# Versie_5.net
KiCad netlist of a schematic drawn in EAGLE
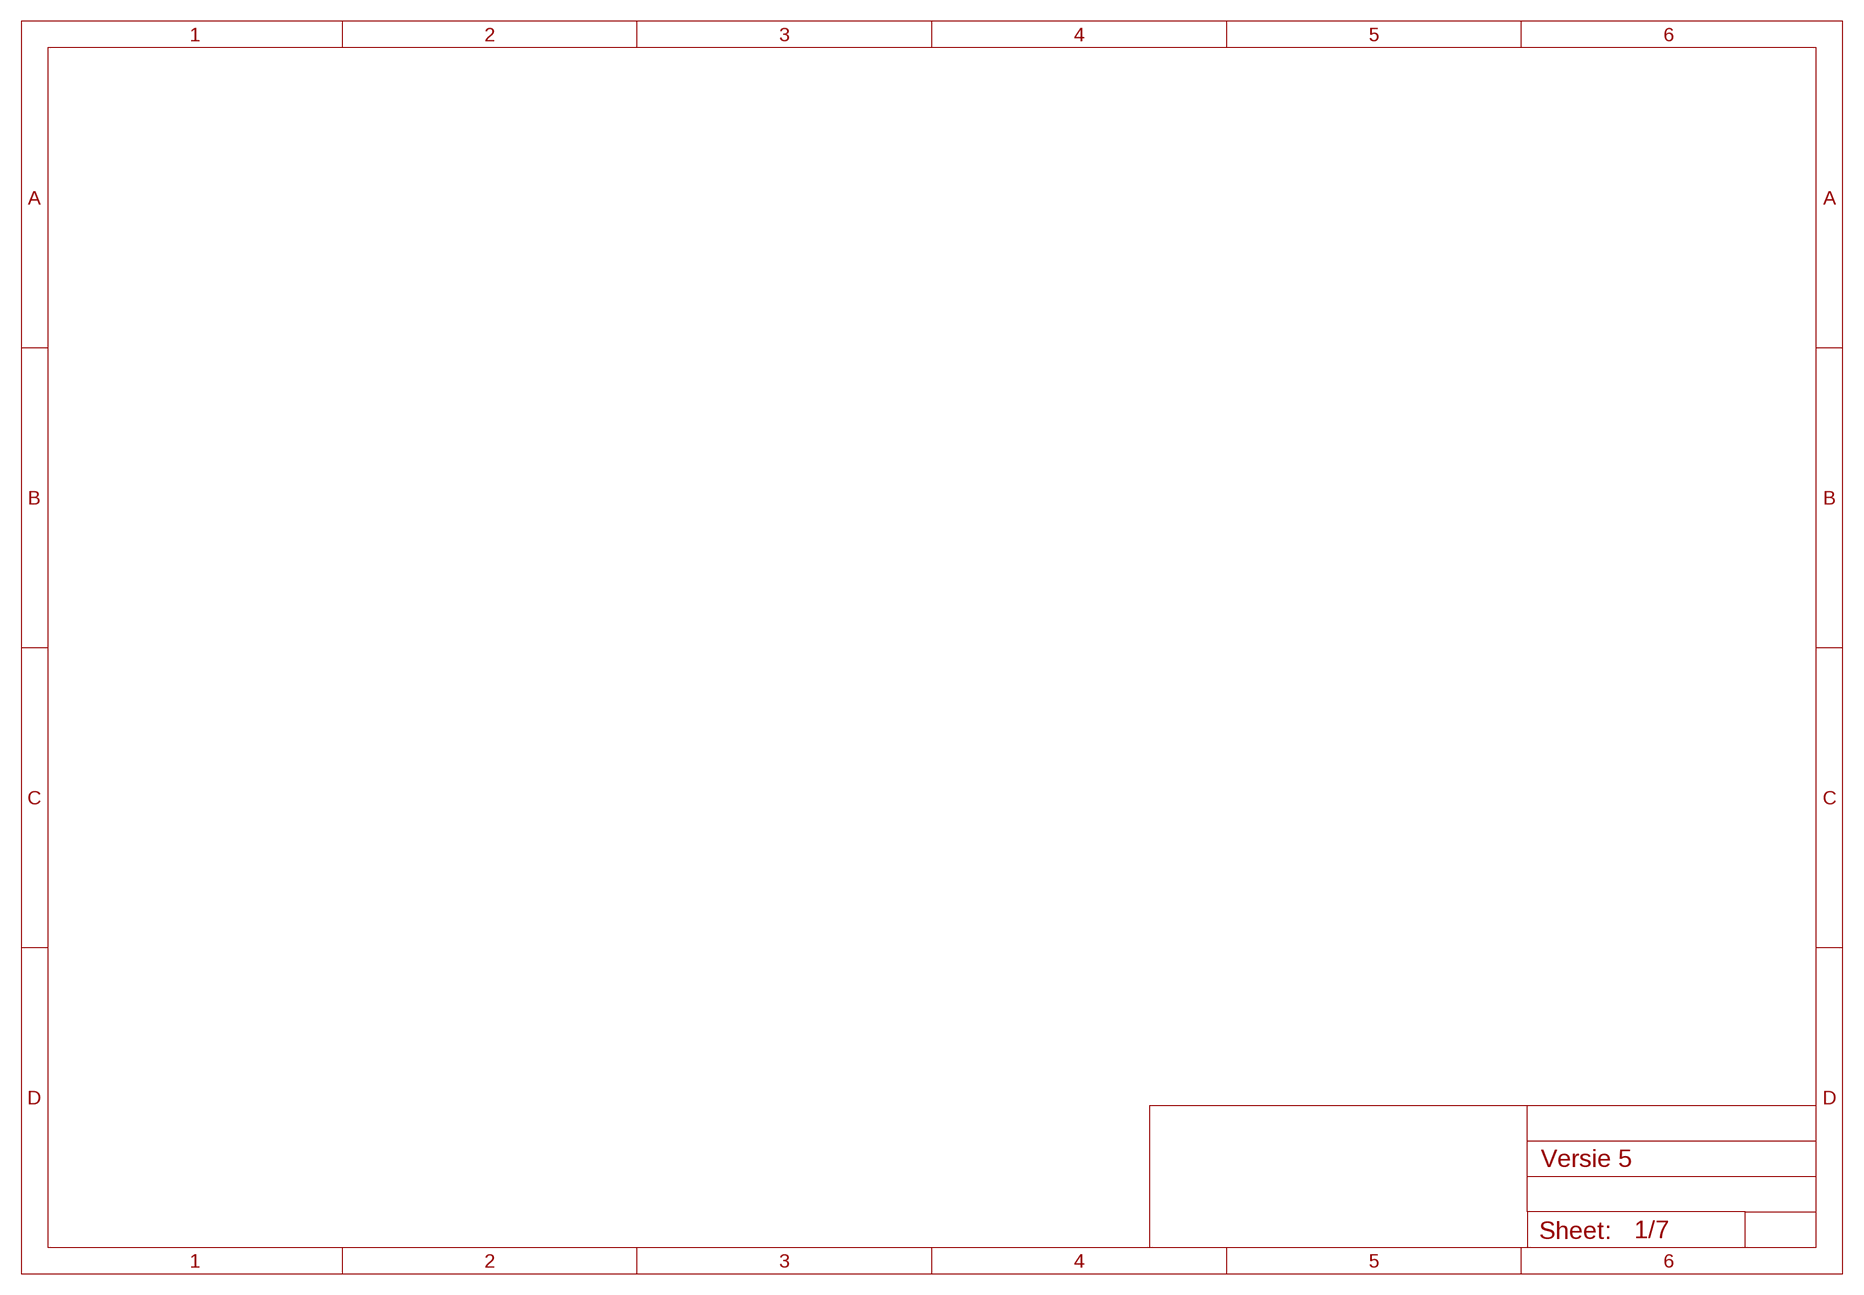
[diagram p0: schematic, sheet 1]
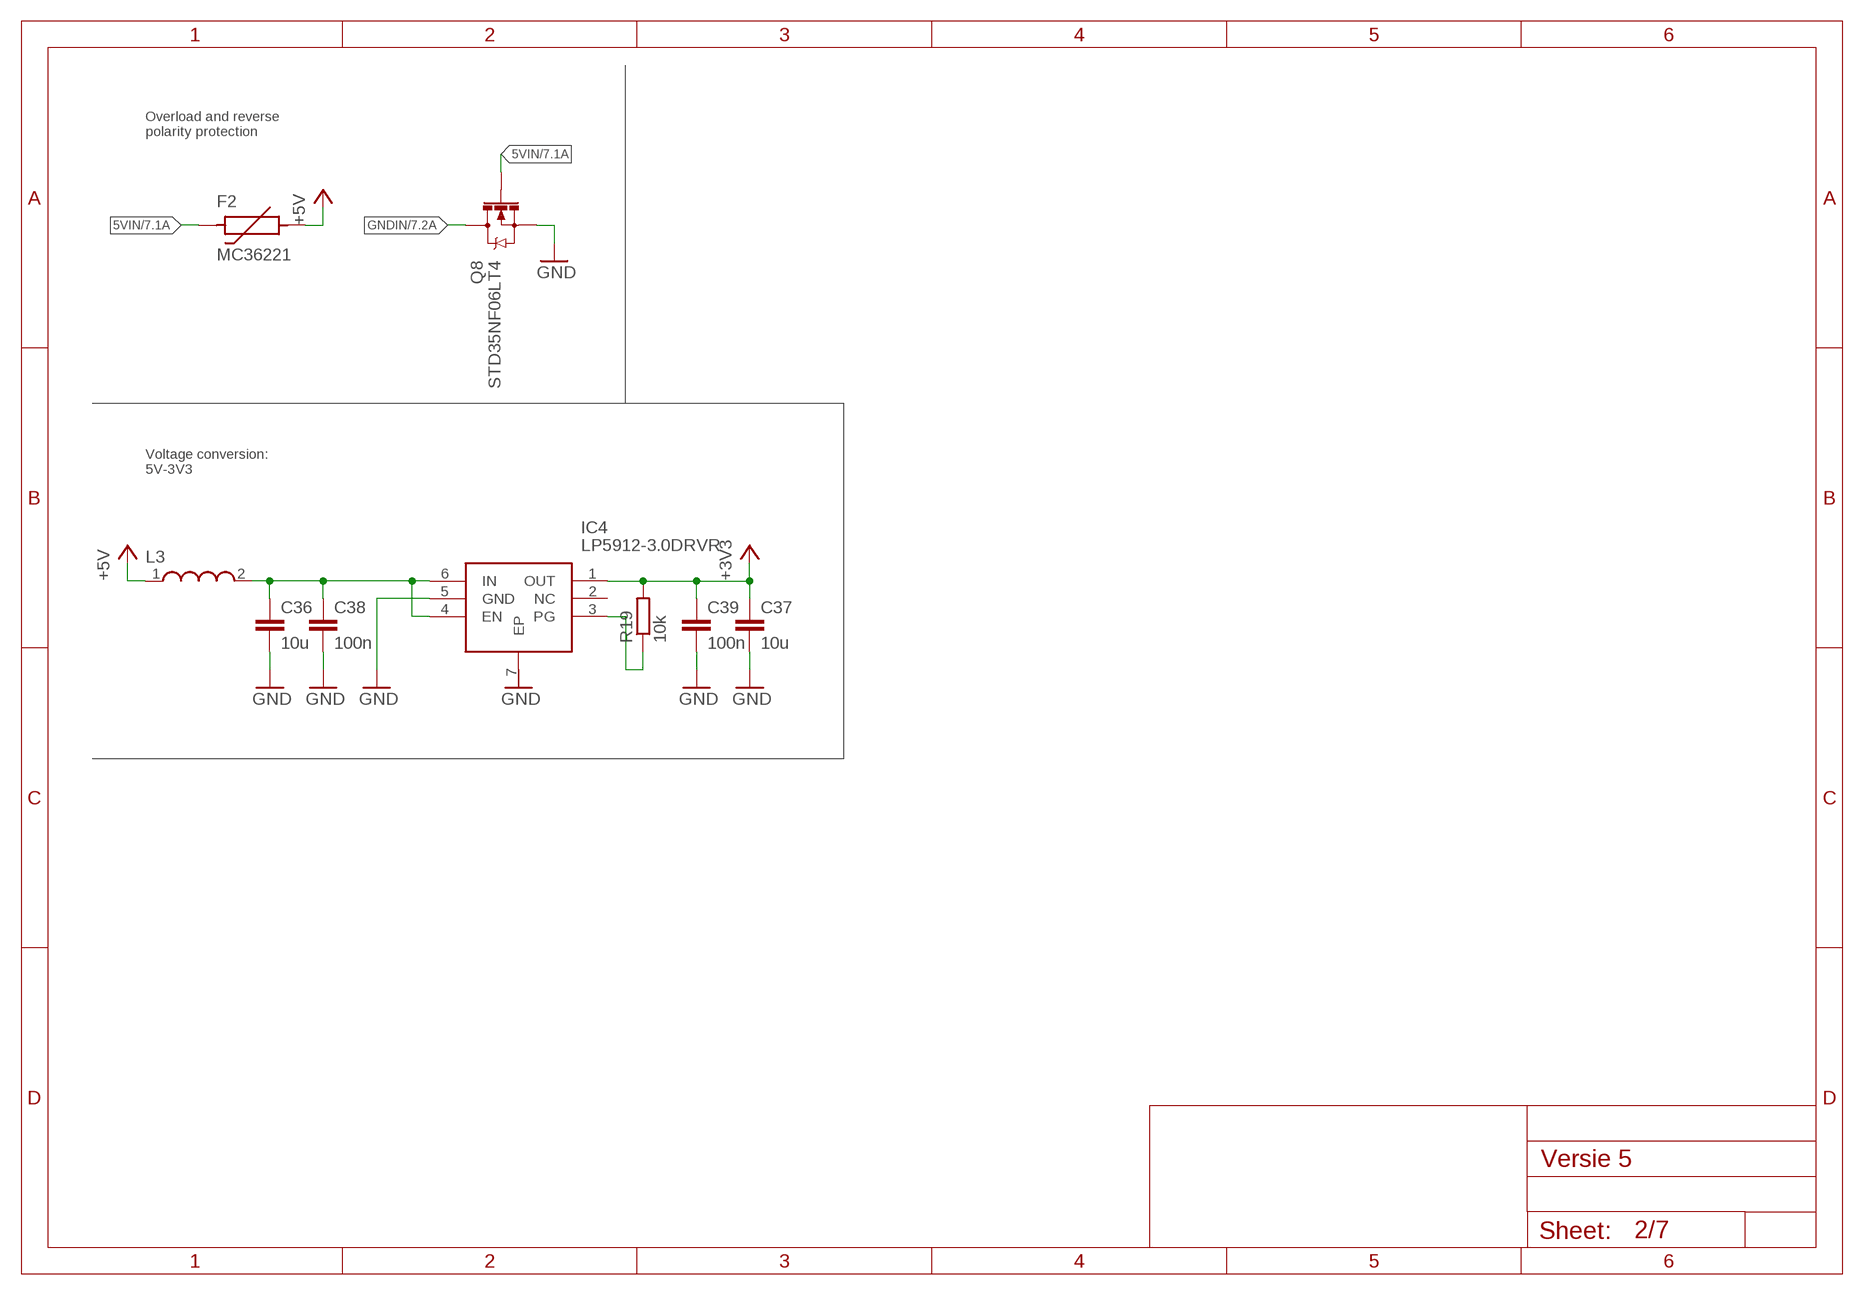
[diagram p1: schematic, sheet 2]
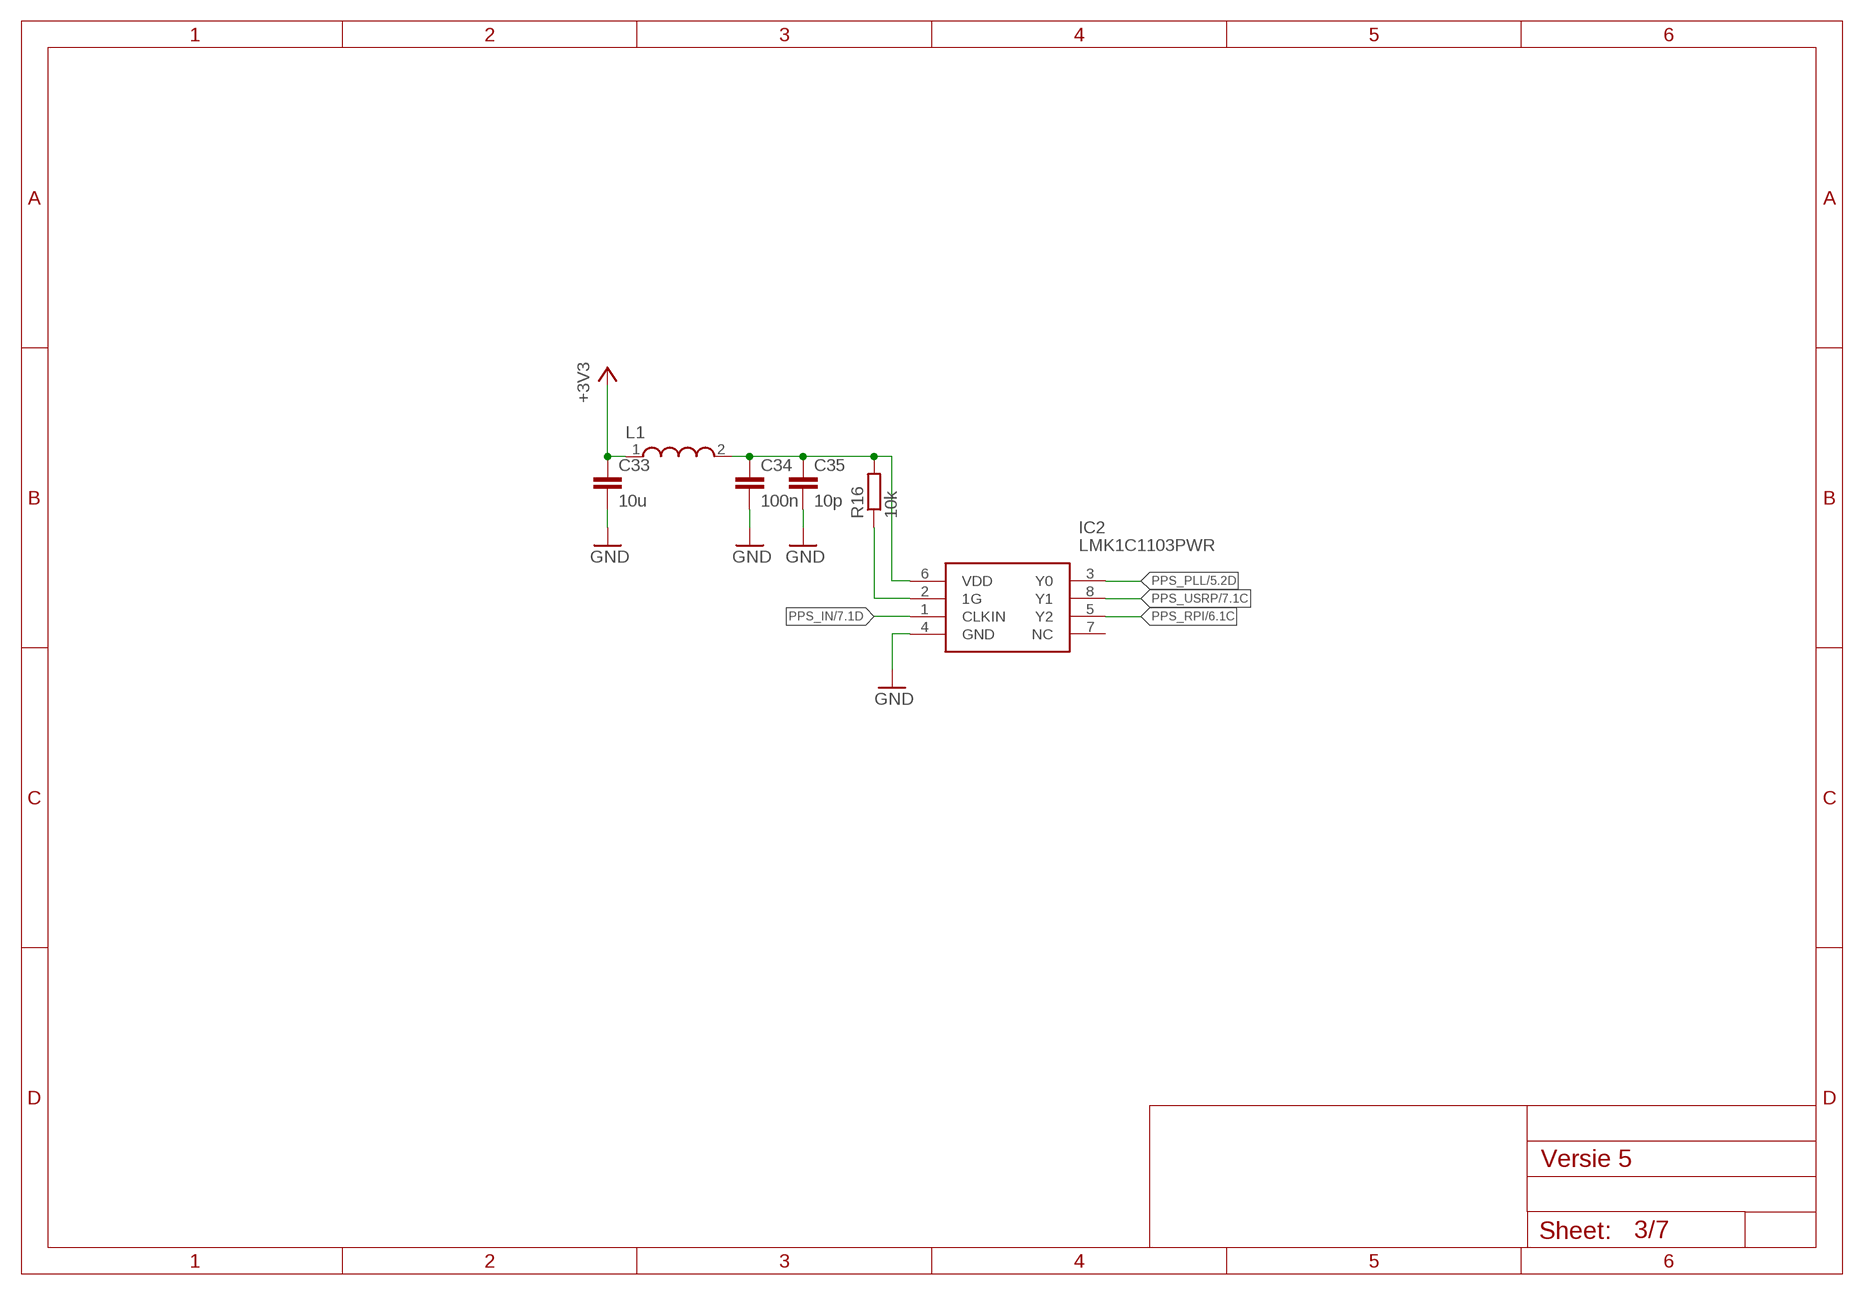
[diagram p2: schematic, sheet 3]
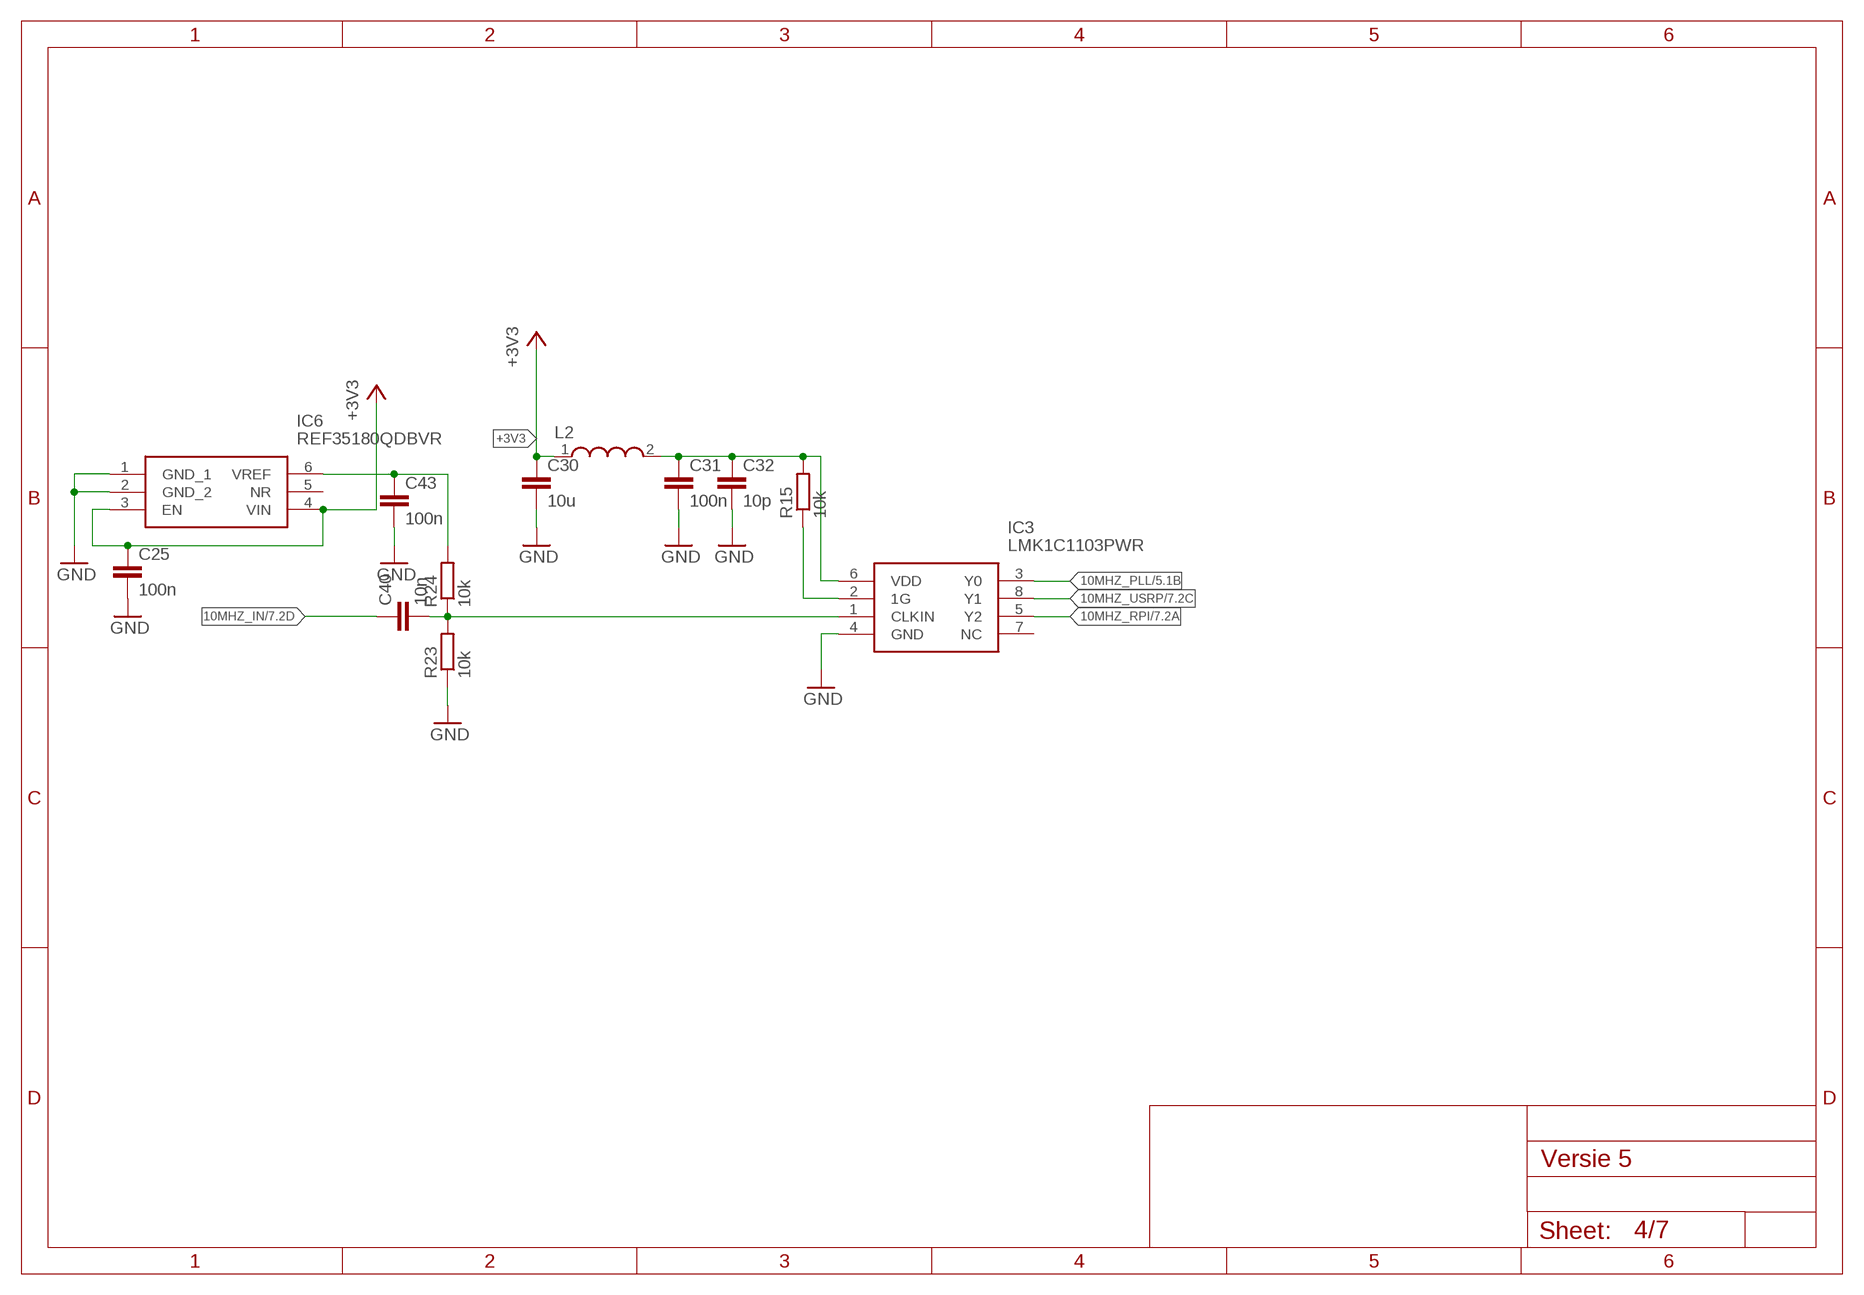
[diagram p3: schematic, sheet 4]
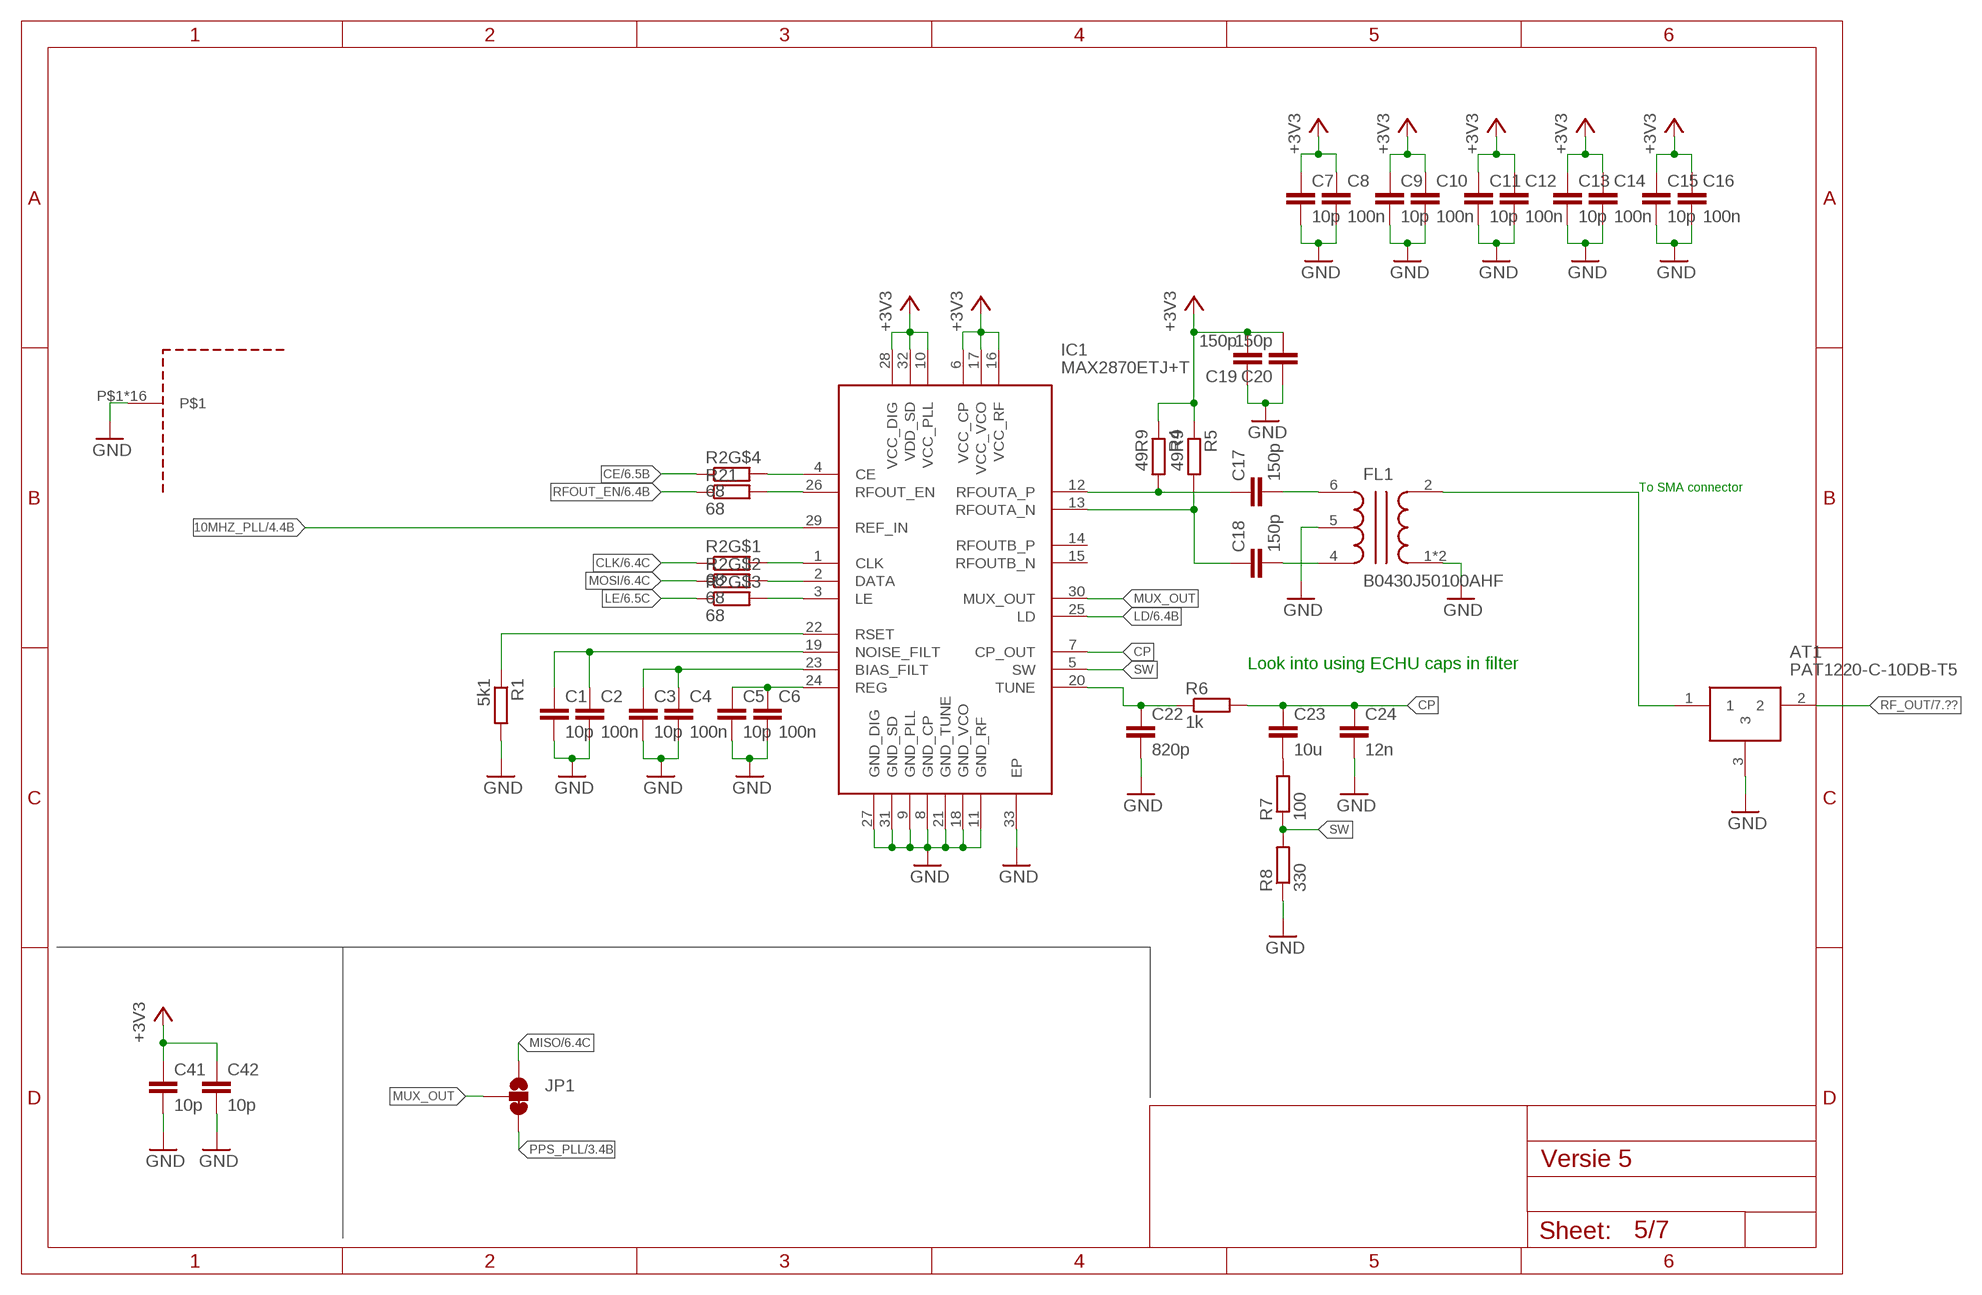
[diagram p4: schematic, sheet 5]
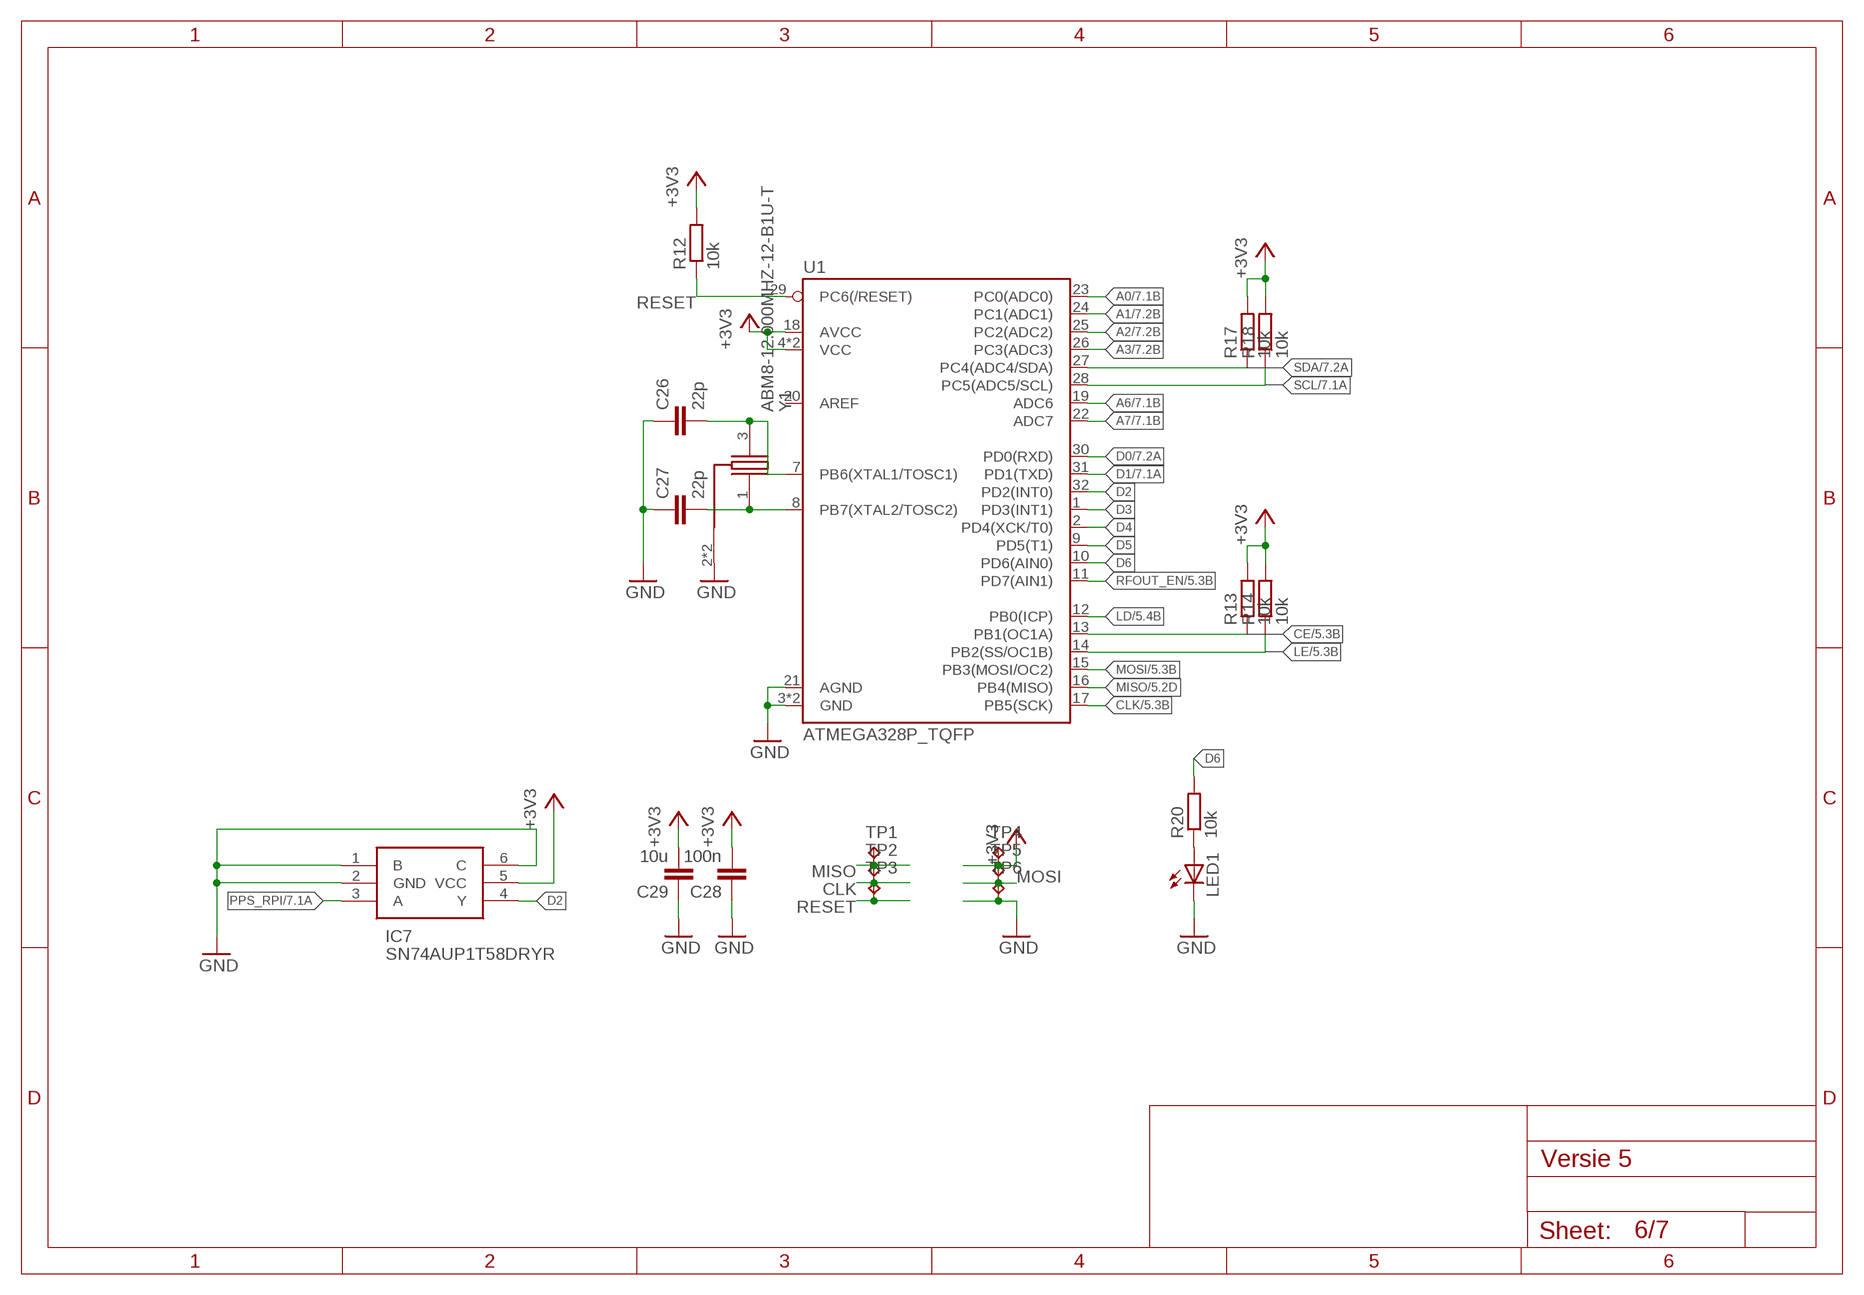
[diagram p5: schematic, sheet 6]
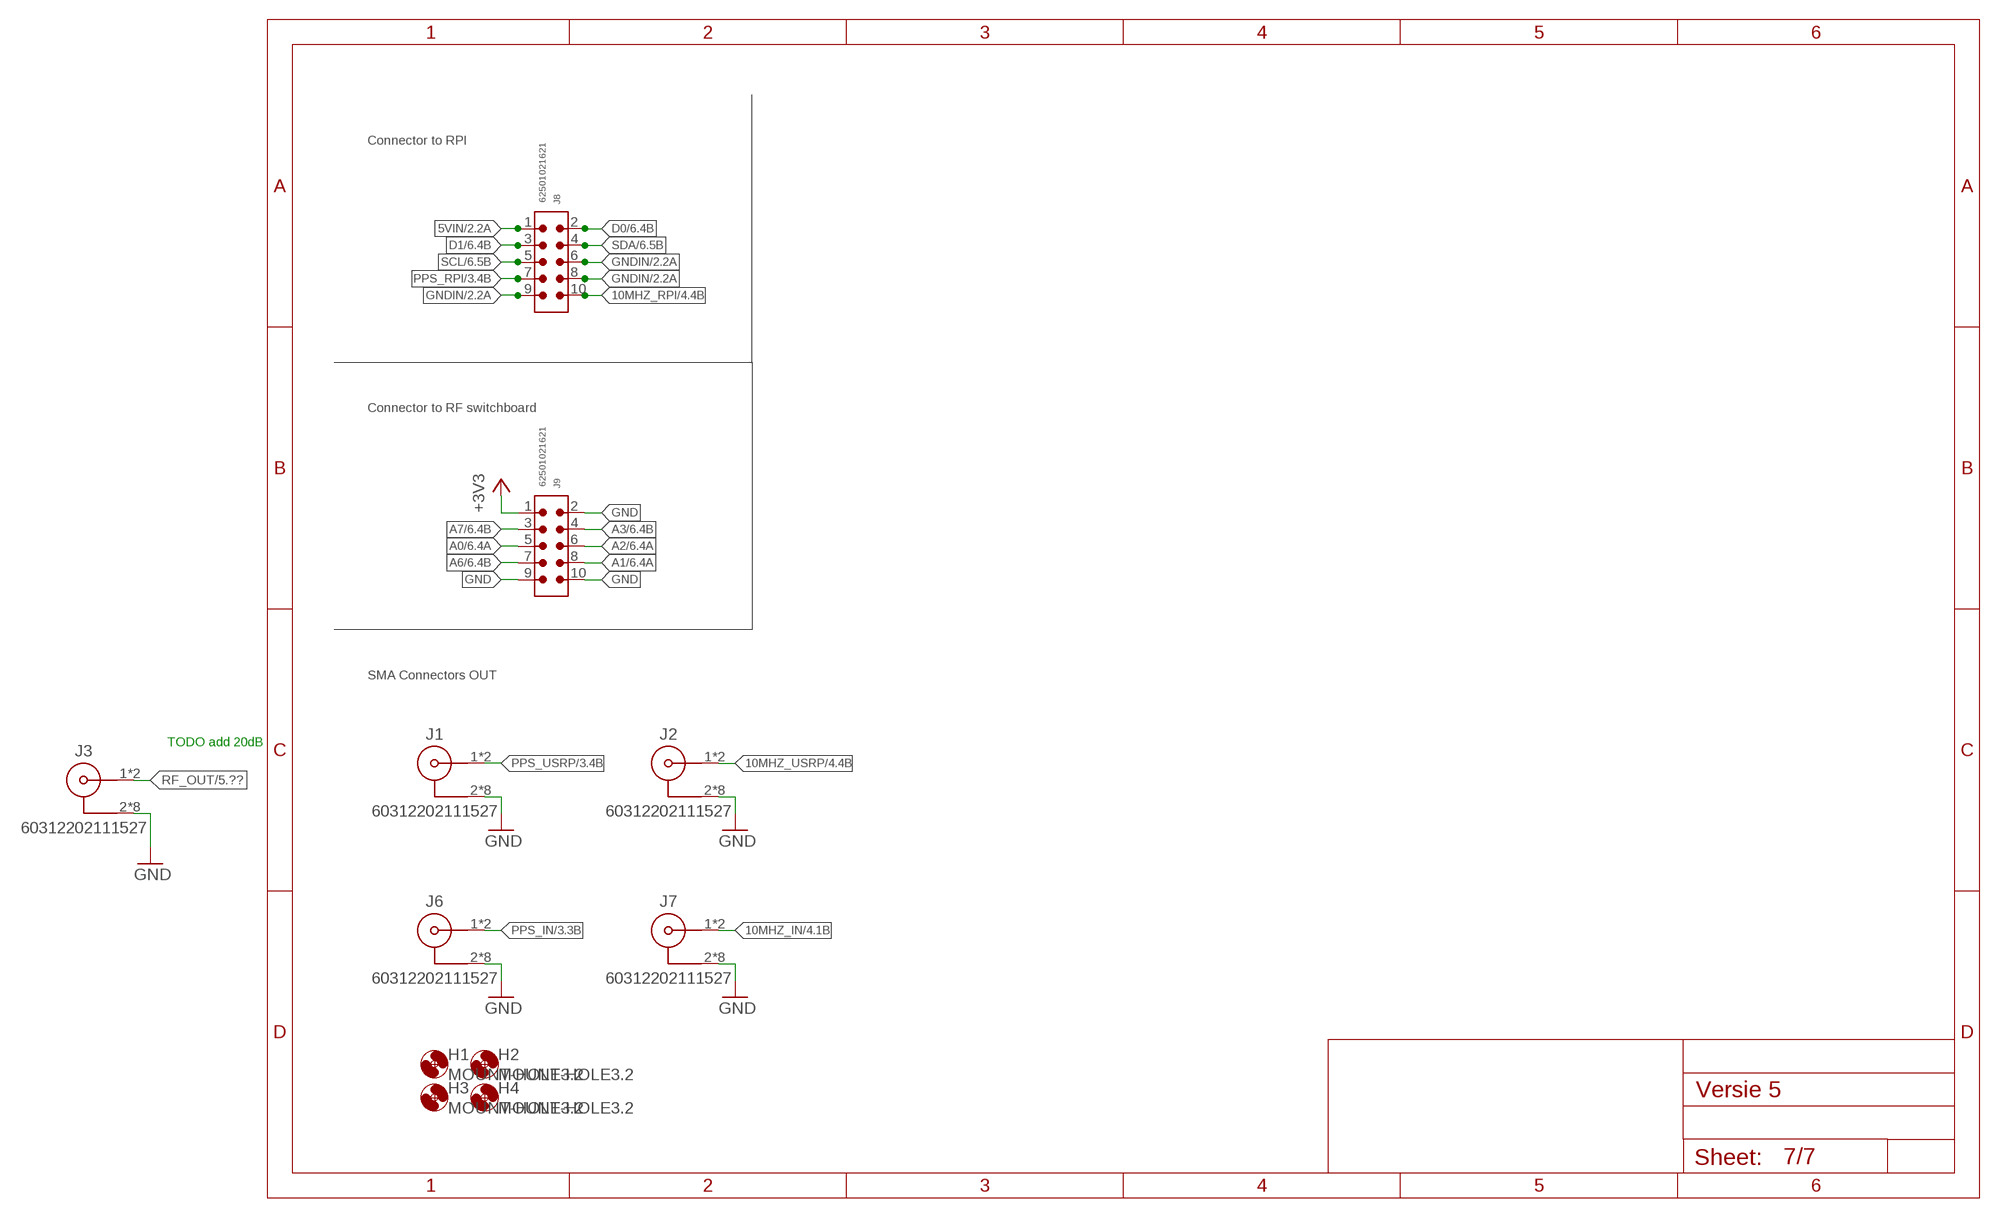
[diagram p6: schematic, sheet 7]

(export (version "E")
  (design (tool "Eeschema 10.0.6"))
  (components
    (comp (ref "C36")
      (value "10u")
      (footprint "eagle-import:C0603")
      (libsource (lib "eagle-import") (part "C-EUC0603"))
    )
    (comp (ref "C37")
      (value "10u")
      (footprint "eagle-import:C0603")
      (libsource (lib "eagle-import") (part "C-EUC0603"))
    )
    (comp (ref "C38")
      (value "100n")
      (footprint "eagle-import:C0603")
      (libsource (lib "eagle-import") (part "C-EUC0603"))
    )
    (comp (ref "C39")
      (value "100n")
      (footprint "eagle-import:C0603")
      (libsource (lib "eagle-import") (part "C-EUC0603"))
    )
    (comp (ref "F2")
      (value "MC36221")
      (footprint "eagle-import:1206")
      (libsource (lib "eagle-import") (part "MC36221"))
    )
    (comp (ref "IC4")
      (value "LP5912-3.0DRVR")
      (footprint "eagle-import:SON65P200X200X80-7N")
      (fields (field (name "MOUSER_PART_NUMBER") "595-LP5912-3.0DRVR"))
      (libsource (lib "eagle-import") (part "LP5912-3.0DRVR"))
    )
    (comp (ref "L3")
      (value "WE-CBA_0603(WB/HS)")
      (footprint "eagle-import:WE-CBA_0603(W=2.2)")
      (libsource (lib "eagle-import") (part "WE-CBA_0603(WB/HS)"))
    )
    (comp (ref "Q8")
      (value "STD35NF06LT4")
      (footprint "eagle-import:SOT23-3")
      (libsource (lib "eagle-import") (part "MOSFET-NCHANNEL_SOT23-3"))
    )
    (comp (ref "R19")
      (value "10k")
      (footprint "eagle-import:R0603")
      (libsource (lib "eagle-import") (part "R-EU_R0603"))
    )
    (comp (ref "C25")
      (value "100n")
      (footprint "eagle-import:C0603")
      (libsource (lib "eagle-import") (part "C-EUC0603"))
    )
    (comp (ref "C30")
      (value "10u")
      (footprint "eagle-import:C0603")
      (libsource (lib "eagle-import") (part "C-EUC0603"))
    )
    (comp (ref "C31")
      (value "100n")
      (footprint "eagle-import:C0603")
      (libsource (lib "eagle-import") (part "C-EUC0603"))
    )
    (comp (ref "C32")
      (value "10p")
      (footprint "eagle-import:C0603")
      (libsource (lib "eagle-import") (part "C-EUC0603"))
    )
    (comp (ref "C40")
      (value "10n")
      (footprint "eagle-import:C0603")
      (libsource (lib "eagle-import") (part "C-EUC0603"))
    )
    (comp (ref "C43")
      (value "100n")
      (footprint "eagle-import:C0603")
      (libsource (lib "eagle-import") (part "C-EUC0603"))
    )
    (comp (ref "IC3")
      (value "LMK1C1103PWR")
      (footprint "eagle-import:SOP65P640X120-8N")
      (fields (field (name "MOUSER_PART_NUMBER") "595-LMK1C1103PWR"))
      (libsource (lib "eagle-import") (part "LMK1C1103PWR"))
    )
    (comp (ref "IC6")
      (value "REF35180QDBVR")
      (footprint "eagle-import:SOT95P280X145-6N")
      (fields (field (name "MOUSER_PART_NUMBER") "595-REF35180QDBVR"))
      (libsource (lib "eagle-import") (part "REF35180QDBVR"))
    )
    (comp (ref "L2")
      (value "WE-CBA_0603(WB/HS)")
      (footprint "eagle-import:WE-CBA_0603(W=2.2)")
      (libsource (lib "eagle-import") (part "WE-CBA_0603(WB/HS)"))
    )
    (comp (ref "R15")
      (value "10k")
      (footprint "eagle-import:R0603")
      (libsource (lib "eagle-import") (part "R-EU_R0603"))
    )
    (comp (ref "R23")
      (value "10k")
      (footprint "eagle-import:R0603")
      (libsource (lib "eagle-import") (part "R-EU_R0603"))
    )
    (comp (ref "R24")
      (value "10k")
      (footprint "eagle-import:R0603")
      (libsource (lib "eagle-import") (part "R-EU_R0603"))
    )
    (comp (ref "C26")
      (value "22p")
      (footprint "eagle-import:C0603")
      (libsource (lib "eagle-import") (part "C-EUC0603"))
    )
    (comp (ref "C27")
      (value "22p")
      (footprint "eagle-import:C0603")
      (libsource (lib "eagle-import") (part "C-EUC0603"))
    )
    (comp (ref "C28")
      (value "100n")
      (footprint "eagle-import:C0603")
      (libsource (lib "eagle-import") (part "C-EUC0603"))
    )
    (comp (ref "C29")
      (value "10u")
      (footprint "eagle-import:C0603")
      (libsource (lib "eagle-import") (part "C-EUC0603"))
    )
    (comp (ref "IC7")
      (value "SN74AUP1T58DRYR")
      (footprint "eagle-import:SON50P100X145X60-6N")
      (libsource (lib "eagle-import") (part "SN74AUP1T58DRYR"))
    )
    (comp (ref "LED1")
      (value "LEDCHIPLED_0805")
      (footprint "eagle-import:CHIPLED_0805")
      (libsource (lib "eagle-import") (part "LEDCHIPLED_0805"))
    )
    (comp (ref "R12")
      (value "10k")
      (footprint "eagle-import:R0603")
      (libsource (lib "eagle-import") (part "R-EU_R0603"))
    )
    (comp (ref "R13")
      (value "10k")
      (footprint "eagle-import:R0603")
      (libsource (lib "eagle-import") (part "R-EU_R0603"))
    )
    (comp (ref "R14")
      (value "10k")
      (footprint "eagle-import:R0603")
      (libsource (lib "eagle-import") (part "R-EU_R0603"))
    )
    (comp (ref "R17")
      (value "10k")
      (footprint "eagle-import:R0603")
      (libsource (lib "eagle-import") (part "R-EU_R0603"))
    )
    (comp (ref "R18")
      (value "10k")
      (footprint "eagle-import:R0603")
      (libsource (lib "eagle-import") (part "R-EU_R0603"))
    )
    (comp (ref "R20")
      (value "10k")
      (footprint "eagle-import:R0603")
      (libsource (lib "eagle-import") (part "R-EU_R0603"))
    )
    (comp (ref "TP1")
      (value "TPTP16R")
      (footprint "eagle-import:TP16R")
      (libsource (lib "eagle-import") (part "TPTP16R"))
    )
    (comp (ref "TP2")
      (value "TPTP16R")
      (footprint "eagle-import:TP16R")
      (libsource (lib "eagle-import") (part "TPTP16R"))
    )
    (comp (ref "TP3")
      (value "TPTP16R")
      (footprint "eagle-import:TP16R")
      (libsource (lib "eagle-import") (part "TPTP16R"))
    )
    (comp (ref "TP4")
      (value "TPTP16R")
      (footprint "eagle-import:TP16R")
      (libsource (lib "eagle-import") (part "TPTP16R"))
    )
    (comp (ref "TP5")
      (value "TPTP16R")
      (footprint "eagle-import:TP16R")
      (libsource (lib "eagle-import") (part "TPTP16R"))
    )
    (comp (ref "TP6")
      (value "TPTP16R")
      (footprint "eagle-import:TP16R")
      (libsource (lib "eagle-import") (part "TPTP16R"))
    )
    (comp (ref "U1")
      (value "ATMEGA328P_TQFP")
      (footprint "eagle-import:TQFP32-08")
      (libsource (lib "eagle-import") (part "ATMEGA328P_TQFP"))
    )
    (comp (ref "Y1")
      (value "ABM8-12.000MHZ-12-B1U-T")
      (footprint "eagle-import:ABM810000MHZ12D2W")
      (fields (field (name "MOUSER_PART_NUMBER") "815-M812000MHZ12B1UT"))
      (libsource (lib "eagle-import") (part "ABM8-12.000MHZ-12-B1U-T"))
    )
    (comp (ref "C33")
      (value "10u")
      (footprint "eagle-import:C0603")
      (libsource (lib "eagle-import") (part "C-EUC0603"))
    )
    (comp (ref "C34")
      (value "100n")
      (footprint "eagle-import:C0603")
      (libsource (lib "eagle-import") (part "C-EUC0603"))
    )
    (comp (ref "C35")
      (value "10p")
      (footprint "eagle-import:C0603")
      (libsource (lib "eagle-import") (part "C-EUC0603"))
    )
    (comp (ref "IC2")
      (value "LMK1C1103PWR")
      (footprint "eagle-import:SOP65P640X120-8N")
      (fields (field (name "MOUSER_PART_NUMBER") "595-LMK1C1103PWR"))
      (libsource (lib "eagle-import") (part "LMK1C1103PWR"))
    )
    (comp (ref "L1")
      (value "WE-CBA_0603(WB/HS)")
      (footprint "eagle-import:WE-CBA_0603(W=2.2)")
      (libsource (lib "eagle-import") (part "WE-CBA_0603(WB/HS)"))
    )
    (comp (ref "R16")
      (value "10k")
      (footprint "eagle-import:R0603")
      (libsource (lib "eagle-import") (part "R-EU_R0603"))
    )
    (comp (ref "AT1")
      (value "PAT1220-C-10DB-T5")
      (footprint "eagle-import:PAT1220C10DBT5")
      (fields (field (name "MOUSER_PART_NUMBER") "754-PAT1220C10DBT5"))
      (libsource (lib "eagle-import") (part "PAT1220-C-10DB-T5"))
    )
    (comp (ref "C1")
      (value "10p")
      (footprint "eagle-import:C0603")
      (libsource (lib "eagle-import") (part "C-EUC0603"))
    )
    (comp (ref "C2")
      (value "100n")
      (footprint "eagle-import:C0603")
      (libsource (lib "eagle-import") (part "C-EUC0603"))
    )
    (comp (ref "C3")
      (value "10p")
      (footprint "eagle-import:C0603")
      (libsource (lib "eagle-import") (part "C-EUC0603"))
    )
    (comp (ref "C4")
      (value "100n")
      (footprint "eagle-import:C0603")
      (libsource (lib "eagle-import") (part "C-EUC0603"))
    )
    (comp (ref "C5")
      (value "10p")
      (footprint "eagle-import:C0603")
      (libsource (lib "eagle-import") (part "C-EUC0603"))
    )
    (comp (ref "C6")
      (value "100n")
      (footprint "eagle-import:C0603")
      (libsource (lib "eagle-import") (part "C-EUC0603"))
    )
    (comp (ref "C7")
      (value "10p")
      (footprint "eagle-import:C0603")
      (libsource (lib "eagle-import") (part "C-EUC0603"))
    )
    (comp (ref "C8")
      (value "100n")
      (footprint "eagle-import:C0603")
      (libsource (lib "eagle-import") (part "C-EUC0603"))
    )
    (comp (ref "C9")
      (value "10p")
      (footprint "eagle-import:C0603")
      (libsource (lib "eagle-import") (part "C-EUC0603"))
    )
    (comp (ref "C10")
      (value "100n")
      (footprint "eagle-import:C0603")
      (libsource (lib "eagle-import") (part "C-EUC0603"))
    )
    (comp (ref "C11")
      (value "10p")
      (footprint "eagle-import:C0603")
      (libsource (lib "eagle-import") (part "C-EUC0603"))
    )
    (comp (ref "C12")
      (value "100n")
      (footprint "eagle-import:C0603")
      (libsource (lib "eagle-import") (part "C-EUC0603"))
    )
    (comp (ref "C13")
      (value "10p")
      (footprint "eagle-import:C0603")
      (libsource (lib "eagle-import") (part "C-EUC0603"))
    )
    (comp (ref "C14")
      (value "100n")
      (footprint "eagle-import:C0603")
      (libsource (lib "eagle-import") (part "C-EUC0603"))
    )
    (comp (ref "C15")
      (value "10p")
      (footprint "eagle-import:C0603")
      (libsource (lib "eagle-import") (part "C-EUC0603"))
    )
    (comp (ref "C16")
      (value "100n")
      (footprint "eagle-import:C0603")
      (libsource (lib "eagle-import") (part "C-EUC0603"))
    )
    (comp (ref "C17")
      (value "150p")
      (footprint "eagle-import:C0402")
      (libsource (lib "eagle-import") (part "C-EUC0402"))
    )
    (comp (ref "C18")
      (value "150p")
      (footprint "eagle-import:C0402")
      (libsource (lib "eagle-import") (part "C-EUC0402"))
    )
    (comp (ref "C19")
      (value "150p")
      (footprint "eagle-import:C0402")
      (libsource (lib "eagle-import") (part "C-EUC0402"))
    )
    (comp (ref "C20")
      (value "150p")
      (footprint "eagle-import:C0402")
      (libsource (lib "eagle-import") (part "C-EUC0402"))
    )
    (comp (ref "C22")
      (value "820p")
      (footprint "eagle-import:C0603")
      (libsource (lib "eagle-import") (part "C-EUC0603"))
    )
    (comp (ref "C23")
      (value "10u")
      (footprint "eagle-import:C0603")
      (libsource (lib "eagle-import") (part "C-EUC0603"))
    )
    (comp (ref "C24")
      (value "12n")
      (footprint "eagle-import:C0603")
      (libsource (lib "eagle-import") (part "C-EUC0603"))
    )
    (comp (ref "C41")
      (value "10p")
      (footprint "eagle-import:C0603")
      (libsource (lib "eagle-import") (part "C-EUC0603"))
    )
    (comp (ref "C42")
      (value "10p")
      (footprint "eagle-import:C0603")
      (libsource (lib "eagle-import") (part "C-EUC0603"))
    )
    (comp (ref "FL1")
      (value "B0430J50100AHF")
      (footprint "eagle-import:B0430J50100AHF")
      (fields (field (name "MOUSER_PART_NUMBER") "620-B0430J50100AHF"))
      (libsource (lib "eagle-import") (part "B0430J50100AHF"))
    )
    (comp (ref "IC1")
      (value "MAX2870ETJ+T")
      (footprint "eagle-import:QFN50P500X500X80-33N")
      (fields (field (name "MOUSER_PART_NUMBER") "700-MAX2870ETJ+T"))
      (libsource (lib "eagle-import") (part "MAX2870ETJ+T"))
    )
    (comp (ref "JP1")
      (value "JUMPER-SMT_3_1-NC_TRACE_SILK")
      (footprint "eagle-import:SMT-JUMPER_3_1-NC_TRACE_SILK")
      (libsource (lib "eagle-import") (part "JUMPER-SMT_3_1-NC_TRACE_SILK"))
    )
    (comp (ref "R1")
      (value "5k1")
      (footprint "eagle-import:R0603")
      (libsource (lib "eagle-import") (part "R-EU_R0603"))
    )
    (comp (ref "R2")
      (value "68")
      (footprint "eagle-import:CAY16A1003F4LF")
      (fields
        (field (name "MANUFACTURER_PART_NUMBER") "CAY16A-2002F4LF")
        (field (name "MOUSER_PART_NUMBER") "652-CAY16A-2002F4LF")
      )
      (libsource (lib "eagle-import") (part "CAY16A-2002F4LF"))
    )
    (comp (ref "R4")
      (value "49R9")
      (footprint "eagle-import:R0402")
      (libsource (lib "eagle-import") (part "R-EU_R0402"))
    )
    (comp (ref "R5")
      (value "49R9")
      (footprint "eagle-import:R0402")
      (libsource (lib "eagle-import") (part "R-EU_R0402"))
    )
    (comp (ref "R6")
      (value "1k")
      (footprint "eagle-import:R0603")
      (libsource (lib "eagle-import") (part "R-EU_R0603"))
    )
    (comp (ref "R7")
      (value "100")
      (footprint "eagle-import:R0603")
      (libsource (lib "eagle-import") (part "R-EU_R0603"))
    )
    (comp (ref "R8")
      (value "330")
      (footprint "eagle-import:R0603")
      (libsource (lib "eagle-import") (part "R-EU_R0603"))
    )
    (comp (ref "R21")
      (value "68")
      (footprint "eagle-import:R0603")
      (libsource (lib "eagle-import") (part "R-EU_R0603"))
    )
    (comp (ref "U$1")
      (value "BMI-S-209-F-20-R")
      (footprint "eagle-import:BMI-S-209-F-20-R")
      (libsource (lib "eagle-import") (part "BMI-S-209-F-20-R"))
    )
    (comp (ref "H1")
      (value "MOUNT-HOLE3.2")
      (footprint "eagle-import:3,2")
      (libsource (lib "eagle-import") (part "MOUNT-HOLE3.2"))
    )
    (comp (ref "H2")
      (value "MOUNT-HOLE3.2")
      (footprint "eagle-import:3,2")
      (libsource (lib "eagle-import") (part "MOUNT-HOLE3.2"))
    )
    (comp (ref "H3")
      (value "MOUNT-HOLE3.2")
      (footprint "eagle-import:3,2")
      (libsource (lib "eagle-import") (part "MOUNT-HOLE3.2"))
    )
    (comp (ref "H4")
      (value "MOUNT-HOLE3.2")
      (footprint "eagle-import:3,2")
      (libsource (lib "eagle-import") (part "MOUNT-HOLE3.2"))
    )
    (comp (ref "J1")
      (value "60312202111527")
      (footprint "eagle-import:60312202111527")
      (libsource (lib "eagle-import") (part "60312202111527"))
    )
    (comp (ref "J2")
      (value "60312202111527")
      (footprint "eagle-import:60312202111527")
      (libsource (lib "eagle-import") (part "60312202111527"))
    )
    (comp (ref "J3")
      (value "60312202111527")
      (footprint "eagle-import:60312202111527")
      (libsource (lib "eagle-import") (part "60312202111527"))
    )
    (comp (ref "J6")
      (value "60312202111527")
      (footprint "eagle-import:60312202111527")
      (libsource (lib "eagle-import") (part "60312202111527"))
    )
    (comp (ref "J7")
      (value "60312202111527")
      (footprint "eagle-import:60312202111527")
      (libsource (lib "eagle-import") (part "60312202111527"))
    )
    (comp (ref "J8")
      (value "62501021621")
      (footprint "eagle-import:62501021621")
      (libsource (lib "eagle-import") (part "6250XX21621_62501021621"))
    )
    (comp (ref "J9")
      (value "62501021621")
      (footprint "eagle-import:62501021621")
      (libsource (lib "eagle-import") (part "6250XX21621_62501021621"))
    )
  )
  (nets
    (net (code "1") (name "+3V3") (class "Default")
      (node (ref "C10") (pin "1") (pinfunction "1_1") (pintype "passive"))
      (node (ref "C11") (pin "1") (pinfunction "1_1") (pintype "passive"))
      (node (ref "C12") (pin "1") (pinfunction "1_1") (pintype "passive"))
      (node (ref "C13") (pin "1") (pinfunction "1_1") (pintype "passive"))
      (node (ref "C14") (pin "1") (pinfunction "1_1") (pintype "passive"))
      (node (ref "C15") (pin "1") (pinfunction "1_1") (pintype "passive"))
      (node (ref "C16") (pin "1") (pinfunction "1_1") (pintype "passive"))
      (node (ref "C19") (pin "2") (pinfunction "2_2") (pintype "passive"))
      (node (ref "C20") (pin "2") (pinfunction "2_2") (pintype "passive"))
      (node (ref "C25") (pin "1") (pinfunction "1_1") (pintype "passive"))
      (node (ref "C28") (pin "2") (pinfunction "2_2") (pintype "passive"))
      (node (ref "C29") (pin "2") (pinfunction "2_2") (pintype "passive"))
      (node (ref "C30") (pin "1") (pinfunction "1_1") (pintype "passive"))
      (node (ref "C33") (pin "1") (pinfunction "1_1") (pintype "passive"))
      (node (ref "C37") (pin "1") (pinfunction "1_1") (pintype "passive"))
      (node (ref "C39") (pin "1") (pinfunction "1_1") (pintype "passive"))
      (node (ref "C41") (pin "1") (pinfunction "1_1") (pintype "passive"))
      (node (ref "C42") (pin "1") (pinfunction "1_1") (pintype "passive"))
      (node (ref "C7") (pin "1") (pinfunction "1_1") (pintype "passive"))
      (node (ref "C8") (pin "1") (pinfunction "1_1") (pintype "passive"))
      (node (ref "C9") (pin "1") (pinfunction "1_1") (pintype "passive"))
      (node (ref "IC1") (pin "10") (pinfunction "VCC_PLL_10") (pintype "bidirectional"))
      (node (ref "IC1") (pin "16") (pinfunction "VCC_RF_16") (pintype "bidirectional"))
      (node (ref "IC1") (pin "17") (pinfunction "VCC_VCO_17") (pintype "bidirectional"))
      (node (ref "IC1") (pin "28") (pinfunction "VCC_DIG_28") (pintype "bidirectional"))
      (node (ref "IC1") (pin "32") (pinfunction "VDD_SD_32") (pintype "bidirectional"))
      (node (ref "IC1") (pin "6") (pinfunction "VCC_CP_6") (pintype "bidirectional"))
      (node (ref "IC4") (pin "1") (pinfunction "OUT_1") (pintype "bidirectional"))
      (node (ref "IC6") (pin "3") (pinfunction "EN_3") (pintype "bidirectional"))
      (node (ref "IC6") (pin "4") (pinfunction "VIN_4") (pintype "bidirectional"))
      (node (ref "IC7") (pin "5") (pinfunction "VCC_5") (pintype "bidirectional"))
      (node (ref "J9") (pin "1") (pinfunction "1_1") (pintype "passive"))
      (node (ref "L1") (pin "1") (pinfunction "1_1") (pintype "passive"))
      (node (ref "L2") (pin "1") (pinfunction "1_1") (pintype "passive"))
      (node (ref "R12") (pin "2") (pinfunction "2_2") (pintype "passive"))
      (node (ref "R13") (pin "2") (pinfunction "2_2") (pintype "passive"))
      (node (ref "R14") (pin "2") (pinfunction "2_2") (pintype "passive"))
      (node (ref "R17") (pin "2") (pinfunction "2_2") (pintype "passive"))
      (node (ref "R18") (pin "2") (pinfunction "2_2") (pintype "passive"))
      (node (ref "R19") (pin "2") (pinfunction "2_2") (pintype "passive"))
      (node (ref "R4") (pin "1") (pinfunction "1_1") (pintype "passive"))
      (node (ref "R5") (pin "1") (pinfunction "1_1") (pintype "passive"))
      (node (ref "TP4") (pin "TP") (pinfunction "TP_TP") (pintype "input"))
      (node (ref "U1") (pin "18") (pinfunction "AVCC_18") (pintype "bidirectional"))
      (node (ref "U1") (pin "4") (pinfunction "VCC_4") (pintype "bidirectional"))
      (node (ref "U1") (pin "6") (pinfunction "VCC_6") (pintype "bidirectional"))
    )
    (net (code "2") (name "+5V") (class "Default")
      (node (ref "F2") (pin "P$2") (pinfunction "P$2_P$2") (pintype "bidirectional"))
      (node (ref "L3") (pin "1") (pinfunction "1_1") (pintype "passive"))
    )
    (net (code "3") (name "5VIN") (class "Default")
      (node (ref "F2") (pin "P$1") (pinfunction "P$1_P$1") (pintype "bidirectional"))
      (node (ref "J8") (pin "1") (pinfunction "1_1") (pintype "passive"))
      (node (ref "Q8") (pin "1") (pinfunction "G_1") (pintype "passive"))
    )
    (net (code "4") (name "10MHZ_IN") (class "Default")
      (node (ref "C40") (pin "1") (pinfunction "1_1") (pintype "passive"))
      (node (ref "J7") (pin "1") (pinfunction "1_1") (pintype "passive"))
      (node (ref "J7") (pin "6") (pinfunction "1_6") (pintype "passive"))
    )
    (net (code "5") (name "10MHZ_PLL") (class "Default")
      (node (ref "IC1") (pin "29") (pinfunction "REF_IN_29") (pintype "bidirectional"))
      (node (ref "IC3") (pin "3") (pinfunction "Y0_3") (pintype "bidirectional"))
    )
    (net (code "6") (name "10MHZ_RPI") (class "Default")
      (node (ref "IC3") (pin "5") (pinfunction "Y2_5") (pintype "bidirectional"))
      (node (ref "J8") (pin "10") (pinfunction "10_10") (pintype "passive"))
    )
    (net (code "7") (name "10MHZ_USRP") (class "Default")
      (node (ref "IC3") (pin "8") (pinfunction "Y1_8") (pintype "bidirectional"))
      (node (ref "J2") (pin "1") (pinfunction "1_1") (pintype "passive"))
      (node (ref "J2") (pin "6") (pinfunction "1_6") (pintype "passive"))
    )
    (net (code "8") (name "A0") (class "Default")
      (node (ref "J9") (pin "5") (pinfunction "5_5") (pintype "passive"))
      (node (ref "U1") (pin "23") (pinfunction "PC0(ADC0)_23") (pintype "bidirectional"))
    )
    (net (code "9") (name "A1") (class "Default")
      (node (ref "J9") (pin "8") (pinfunction "8_8") (pintype "passive"))
      (node (ref "U1") (pin "24") (pinfunction "PC1(ADC1)_24") (pintype "bidirectional"))
    )
    (net (code "10") (name "A2") (class "Default")
      (node (ref "J9") (pin "6") (pinfunction "6_6") (pintype "passive"))
      (node (ref "U1") (pin "25") (pinfunction "PC2(ADC2)_25") (pintype "bidirectional"))
    )
    (net (code "11") (name "A3") (class "Default")
      (node (ref "J9") (pin "4") (pinfunction "4_4") (pintype "passive"))
      (node (ref "U1") (pin "26") (pinfunction "PC3(ADC3)_26") (pintype "bidirectional"))
    )
    (net (code "12") (name "A6") (class "Default")
      (node (ref "J9") (pin "7") (pinfunction "7_7") (pintype "passive"))
      (node (ref "U1") (pin "19") (pinfunction "ADC6_19") (pintype "bidirectional"))
    )
    (net (code "13") (name "A7") (class "Default")
      (node (ref "J9") (pin "3") (pinfunction "3_3") (pintype "passive"))
      (node (ref "U1") (pin "22") (pinfunction "ADC7_22") (pintype "bidirectional"))
    )
    (net (code "14") (name "CE") (class "Default")
      (node (ref "R13") (pin "1") (pinfunction "1_1") (pintype "passive"))
      (node (ref "R2") (pin "4") (pinfunction "1_4") (pintype "passive"))
      (node (ref "U1") (pin "13") (pinfunction "PB1(OC1A)_13") (pintype "bidirectional"))
    )
    (net (code "15") (name "CLK") (class "Default")
      (node (ref "R2") (pin "1") (pinfunction "1_1") (pintype "passive"))
      (node (ref "TP2") (pin "TP") (pinfunction "TP_TP") (pintype "input"))
      (node (ref "U1") (pin "17") (pinfunction "PB5(SCK)_17") (pintype "bidirectional"))
    )
    (net (code "16") (name "CP") (class "Default")
      (node (ref "C23") (pin "1") (pinfunction "1_1") (pintype "passive"))
      (node (ref "C24") (pin "1") (pinfunction "1_1") (pintype "passive"))
      (node (ref "IC1") (pin "7") (pinfunction "CP_OUT_7") (pintype "bidirectional"))
      (node (ref "R6") (pin "2") (pinfunction "2_2") (pintype "passive"))
    )
    (net (code "17") (name "D0") (class "Default")
      (node (ref "J8") (pin "2") (pinfunction "2_2") (pintype "passive"))
      (node (ref "U1") (pin "30") (pinfunction "PD0(RXD)_30") (pintype "bidirectional"))
    )
    (net (code "18") (name "D1") (class "Default")
      (node (ref "J8") (pin "3") (pinfunction "3_3") (pintype "passive"))
      (node (ref "U1") (pin "31") (pinfunction "PD1(TXD)_31") (pintype "bidirectional"))
    )
    (net (code "19") (name "D2") (class "Default")
      (node (ref "IC7") (pin "4") (pinfunction "Y_4") (pintype "bidirectional"))
      (node (ref "U1") (pin "32") (pinfunction "PD2(INT0)_32") (pintype "bidirectional"))
    )
    (net (code "20") (name "D3") (class "Default")
      (node (ref "U1") (pin "1") (pinfunction "PD3(INT1)_1") (pintype "bidirectional"))
    )
    (net (code "21") (name "D4") (class "Default")
      (node (ref "U1") (pin "2") (pinfunction "PD4(XCK/T0)_2") (pintype "bidirectional"))
    )
    (net (code "22") (name "D5") (class "Default")
      (node (ref "U1") (pin "9") (pinfunction "PD5(T1)_9") (pintype "bidirectional"))
    )
    (net (code "23") (name "D6") (class "Default")
      (node (ref "R20") (pin "2") (pinfunction "2_2") (pintype "passive"))
      (node (ref "U1") (pin "10") (pinfunction "PD6(AIN0)_10") (pintype "bidirectional"))
    )
    (net (code "24") (name "GND") (class "Default")
      (node (ref "AT1") (pin "3") (pinfunction "3_3") (pintype "bidirectional"))
      (node (ref "C1") (pin "2") (pinfunction "2_2") (pintype "passive"))
      (node (ref "C10") (pin "2") (pinfunction "2_2") (pintype "passive"))
      (node (ref "C11") (pin "2") (pinfunction "2_2") (pintype "passive"))
      (node (ref "C12") (pin "2") (pinfunction "2_2") (pintype "passive"))
      (node (ref "C13") (pin "2") (pinfunction "2_2") (pintype "passive"))
      (node (ref "C14") (pin "2") (pinfunction "2_2") (pintype "passive"))
      (node (ref "C15") (pin "2") (pinfunction "2_2") (pintype "passive"))
      (node (ref "C16") (pin "2") (pinfunction "2_2") (pintype "passive"))
      (node (ref "C19") (pin "1") (pinfunction "1_1") (pintype "passive"))
      (node (ref "C2") (pin "2") (pinfunction "2_2") (pintype "passive"))
      (node (ref "C20") (pin "1") (pinfunction "1_1") (pintype "passive"))
      (node (ref "C22") (pin "2") (pinfunction "2_2") (pintype "passive"))
      (node (ref "C24") (pin "2") (pinfunction "2_2") (pintype "passive"))
      (node (ref "C25") (pin "2") (pinfunction "2_2") (pintype "passive"))
      (node (ref "C26") (pin "1") (pinfunction "1_1") (pintype "passive"))
      (node (ref "C27") (pin "1") (pinfunction "1_1") (pintype "passive"))
      (node (ref "C28") (pin "1") (pinfunction "1_1") (pintype "passive"))
      (node (ref "C29") (pin "1") (pinfunction "1_1") (pintype "passive"))
      (node (ref "C3") (pin "2") (pinfunction "2_2") (pintype "passive"))
      (node (ref "C30") (pin "2") (pinfunction "2_2") (pintype "passive"))
      (node (ref "C31") (pin "2") (pinfunction "2_2") (pintype "passive"))
      (node (ref "C32") (pin "2") (pinfunction "2_2") (pintype "passive"))
      (node (ref "C33") (pin "2") (pinfunction "2_2") (pintype "passive"))
      (node (ref "C34") (pin "2") (pinfunction "2_2") (pintype "passive"))
      (node (ref "C35") (pin "2") (pinfunction "2_2") (pintype "passive"))
      (node (ref "C36") (pin "2") (pinfunction "2_2") (pintype "passive"))
      (node (ref "C37") (pin "2") (pinfunction "2_2") (pintype "passive"))
      (node (ref "C38") (pin "2") (pinfunction "2_2") (pintype "passive"))
      (node (ref "C39") (pin "2") (pinfunction "2_2") (pintype "passive"))
      (node (ref "C4") (pin "2") (pinfunction "2_2") (pintype "passive"))
      (node (ref "C41") (pin "2") (pinfunction "2_2") (pintype "passive"))
      (node (ref "C42") (pin "2") (pinfunction "2_2") (pintype "passive"))
      (node (ref "C43") (pin "2") (pinfunction "2_2") (pintype "passive"))
      (node (ref "C5") (pin "2") (pinfunction "2_2") (pintype "passive"))
      (node (ref "C6") (pin "2") (pinfunction "2_2") (pintype "passive"))
      (node (ref "C7") (pin "2") (pinfunction "2_2") (pintype "passive"))
      (node (ref "C8") (pin "2") (pinfunction "2_2") (pintype "passive"))
      (node (ref "C9") (pin "2") (pinfunction "2_2") (pintype "passive"))
      (node (ref "FL1") (pin "1") (pinfunction "GND_1_1") (pintype "bidirectional"))
      (node (ref "FL1") (pin "3") (pinfunction "GND_1_3") (pintype "bidirectional"))
      (node (ref "FL1") (pin "5") (pinfunction "NC_5") (pintype "bidirectional"))
      (node (ref "IC1") (pin "11") (pinfunction "GND_RF_11") (pintype "bidirectional"))
      (node (ref "IC1") (pin "18") (pinfunction "GND_VCO_18") (pintype "bidirectional"))
      (node (ref "IC1") (pin "21") (pinfunction "GND_TUNE_21") (pintype "bidirectional"))
      (node (ref "IC1") (pin "27") (pinfunction "GND_DIG_27") (pintype "bidirectional"))
      (node (ref "IC1") (pin "31") (pinfunction "GND_SD_31") (pintype "bidirectional"))
      (node (ref "IC1") (pin "33") (pinfunction "EP_33") (pintype "bidirectional"))
      (node (ref "IC1") (pin "8") (pinfunction "GND_CP_8") (pintype "bidirectional"))
      (node (ref "IC1") (pin "9") (pinfunction "GND_PLL_9") (pintype "bidirectional"))
      (node (ref "IC2") (pin "4") (pinfunction "GND_4") (pintype "bidirectional"))
      (node (ref "IC3") (pin "4") (pinfunction "GND_4") (pintype "bidirectional"))
      (node (ref "IC4") (pin "5") (pinfunction "GND_5") (pintype "bidirectional"))
      (node (ref "IC6") (pin "1") (pinfunction "GND_1_1") (pintype "bidirectional"))
      (node (ref "IC6") (pin "2") (pinfunction "GND_2_2") (pintype "bidirectional"))
      (node (ref "IC7") (pin "1") (pinfunction "B_1") (pintype "bidirectional"))
      (node (ref "IC7") (pin "2") (pinfunction "GND_2") (pintype "bidirectional"))
      (node (ref "IC7") (pin "6") (pinfunction "C_6") (pintype "bidirectional"))
      (node (ref "J1") (pin "10") (pinfunction "2_10") (pintype "passive"))
      (node (ref "J1") (pin "2") (pinfunction "2_2") (pintype "passive"))
      (node (ref "J1") (pin "3") (pinfunction "2_3") (pintype "passive"))
      (node (ref "J1") (pin "4") (pinfunction "2_4") (pintype "passive"))
      (node (ref "J1") (pin "5") (pinfunction "2_5") (pintype "passive"))
      (node (ref "J1") (pin "7") (pinfunction "2_7") (pintype "passive"))
      (node (ref "J1") (pin "8") (pinfunction "2_8") (pintype "passive"))
      (node (ref "J1") (pin "9") (pinfunction "2_9") (pintype "passive"))
      (node (ref "J2") (pin "10") (pinfunction "2_10") (pintype "passive"))
      (node (ref "J2") (pin "2") (pinfunction "2_2") (pintype "passive"))
      (node (ref "J2") (pin "3") (pinfunction "2_3") (pintype "passive"))
      (node (ref "J2") (pin "4") (pinfunction "2_4") (pintype "passive"))
      (node (ref "J2") (pin "5") (pinfunction "2_5") (pintype "passive"))
      (node (ref "J2") (pin "7") (pinfunction "2_7") (pintype "passive"))
      (node (ref "J2") (pin "8") (pinfunction "2_8") (pintype "passive"))
      (node (ref "J2") (pin "9") (pinfunction "2_9") (pintype "passive"))
      (node (ref "J3") (pin "10") (pinfunction "2_10") (pintype "passive"))
      (node (ref "J3") (pin "2") (pinfunction "2_2") (pintype "passive"))
      (node (ref "J3") (pin "3") (pinfunction "2_3") (pintype "passive"))
      (node (ref "J3") (pin "4") (pinfunction "2_4") (pintype "passive"))
      (node (ref "J3") (pin "5") (pinfunction "2_5") (pintype "passive"))
      (node (ref "J3") (pin "7") (pinfunction "2_7") (pintype "passive"))
      (node (ref "J3") (pin "8") (pinfunction "2_8") (pintype "passive"))
      (node (ref "J3") (pin "9") (pinfunction "2_9") (pintype "passive"))
      (node (ref "J6") (pin "10") (pinfunction "2_10") (pintype "passive"))
      (node (ref "J6") (pin "2") (pinfunction "2_2") (pintype "passive"))
      (node (ref "J6") (pin "3") (pinfunction "2_3") (pintype "passive"))
      (node (ref "J6") (pin "4") (pinfunction "2_4") (pintype "passive"))
      (node (ref "J6") (pin "5") (pinfunction "2_5") (pintype "passive"))
      (node (ref "J6") (pin "7") (pinfunction "2_7") (pintype "passive"))
      (node (ref "J6") (pin "8") (pinfunction "2_8") (pintype "passive"))
      (node (ref "J6") (pin "9") (pinfunction "2_9") (pintype "passive"))
      (node (ref "J7") (pin "10") (pinfunction "2_10") (pintype "passive"))
      (node (ref "J7") (pin "2") (pinfunction "2_2") (pintype "passive"))
      (node (ref "J7") (pin "3") (pinfunction "2_3") (pintype "passive"))
      (node (ref "J7") (pin "4") (pinfunction "2_4") (pintype "passive"))
      (node (ref "J7") (pin "5") (pinfunction "2_5") (pintype "passive"))
      (node (ref "J7") (pin "7") (pinfunction "2_7") (pintype "passive"))
      (node (ref "J7") (pin "8") (pinfunction "2_8") (pintype "passive"))
      (node (ref "J7") (pin "9") (pinfunction "2_9") (pintype "passive"))
      (node (ref "J9") (pin "10") (pinfunction "10_10") (pintype "passive"))
      (node (ref "J9") (pin "2") (pinfunction "2_2") (pintype "passive"))
      (node (ref "J9") (pin "9") (pinfunction "9_9") (pintype "passive"))
      (node (ref "LED1") (pin "C") (pinfunction "C_C") (pintype "passive"))
      (node (ref "Q8") (pin "2") (pinfunction "S_2") (pintype "passive"))
      (node (ref "R1") (pin "2") (pinfunction "2_2") (pintype "passive"))
      (node (ref "R23") (pin "1") (pinfunction "1_1") (pintype "passive"))
      (node (ref "R8") (pin "1") (pinfunction "1_1") (pintype "passive"))
      (node (ref "TP6") (pin "TP") (pinfunction "TP_TP") (pintype "input"))
      (node (ref "U$1") (pin "P$1") (pinfunction "P$1_P$1") (pintype "bidirectional"))
      (node (ref "U$1") (pin "P$10") (pinfunction "P$1_P$10") (pintype "bidirectional"))
      (node (ref "U$1") (pin "P$11") (pinfunction "P$1_P$11") (pintype "bidirectional"))
      (node (ref "U$1") (pin "P$12") (pinfunction "P$1_P$12") (pintype "bidirectional"))
      (node (ref "U$1") (pin "P$13") (pinfunction "P$1_P$13") (pintype "bidirectional"))
      (node (ref "U$1") (pin "P$14") (pinfunction "P$1_P$14") (pintype "bidirectional"))
      (node (ref "U$1") (pin "P$15") (pinfunction "P$1_P$15") (pintype "bidirectional"))
      (node (ref "U$1") (pin "P$16") (pinfunction "P$1_P$16") (pintype "bidirectional"))
      (node (ref "U$1") (pin "P$2") (pinfunction "P$1_P$2") (pintype "bidirectional"))
      (node (ref "U$1") (pin "P$3") (pinfunction "P$1_P$3") (pintype "bidirectional"))
      (node (ref "U$1") (pin "P$4") (pinfunction "P$1_P$4") (pintype "bidirectional"))
      (node (ref "U$1") (pin "P$5") (pinfunction "P$1_P$5") (pintype "bidirectional"))
      (node (ref "U$1") (pin "P$6") (pinfunction "P$1_P$6") (pintype "bidirectional"))
      (node (ref "U$1") (pin "P$7") (pinfunction "P$1_P$7") (pintype "bidirectional"))
      (node (ref "U$1") (pin "P$8") (pinfunction "P$1_P$8") (pintype "bidirectional"))
      (node (ref "U$1") (pin "P$9") (pinfunction "P$1_P$9") (pintype "bidirectional"))
      (node (ref "U1") (pin "21") (pinfunction "AGND_21") (pintype "bidirectional"))
      (node (ref "U1") (pin "3") (pinfunction "GND_3") (pintype "bidirectional"))
      (node (ref "U1") (pin "5") (pinfunction "GND_5") (pintype "bidirectional"))
      (node (ref "Y1") (pin "2") (pinfunction "GND_1_2") (pintype "bidirectional"))
      (node (ref "Y1") (pin "4") (pinfunction "GND_1_4") (pintype "bidirectional"))
    )
    (net (code "25") (name "GNDIN") (class "Default")
      (node (ref "J8") (pin "6") (pinfunction "6_6") (pintype "passive"))
      (node (ref "J8") (pin "8") (pinfunction "8_8") (pintype "passive"))
      (node (ref "J8") (pin "9") (pinfunction "9_9") (pintype "passive"))
      (node (ref "Q8") (pin "3") (pinfunction "D_3") (pintype "passive"))
    )
    (net (code "26") (name "LD") (class "Default")
      (node (ref "IC1") (pin "25") (pinfunction "LD_25") (pintype "bidirectional"))
      (node (ref "U1") (pin "12") (pinfunction "PB0(ICP)_12") (pintype "bidirectional"))
    )
    (net (code "27") (name "LE") (class "Default")
      (node (ref "R14") (pin "1") (pinfunction "1_1") (pintype "passive"))
      (node (ref "R2") (pin "3") (pinfunction "1_3") (pintype "passive"))
      (node (ref "U1") (pin "14") (pinfunction "PB2(SS/OC1B)_14") (pintype "bidirectional"))
    )
    (net (code "28") (name "MISO") (class "Default")
      (node (ref "JP1") (pin "1") (pinfunction "1_1") (pintype "passive"))
      (node (ref "TP1") (pin "TP") (pinfunction "TP_TP") (pintype "input"))
      (node (ref "U1") (pin "16") (pinfunction "PB4(MISO)_16") (pintype "bidirectional"))
    )
    (net (code "29") (name "MOSI") (class "Default")
      (node (ref "R2") (pin "2") (pinfunction "1_2") (pintype "passive"))
      (node (ref "TP5") (pin "TP") (pinfunction "TP_TP") (pintype "input"))
      (node (ref "U1") (pin "15") (pinfunction "PB3(MOSI/OC2)_15") (pintype "bidirectional"))
    )
    (net (code "30") (name "MUX_OUT") (class "Default")
      (node (ref "IC1") (pin "30") (pinfunction "MUX_OUT_30") (pintype "bidirectional"))
      (node (ref "JP1") (pin "2") (pinfunction "2_2") (pintype "passive"))
    )
    (net (code "31") (name "Net-(C23-Pad2)") (class "Default")
      (node (ref "C23") (pin "2") (pinfunction "2_2") (pintype "passive"))
      (node (ref "R7") (pin "2") (pinfunction "2_2") (pintype "passive"))
    )
    (net (code "32") (name "Net-(FL1-BALANCED_PORT_1)") (class "Default")
      (node (ref "C18") (pin "2") (pinfunction "2_2") (pintype "passive"))
      (node (ref "FL1") (pin "4") (pinfunction "BALANCED_PORT_1_4") (pintype "bidirectional"))
    )
    (net (code "33") (name "Net-(FL1-BALANCED_PORT_2)") (class "Default")
      (node (ref "C17") (pin "2") (pinfunction "2_2") (pintype "passive"))
      (node (ref "FL1") (pin "6") (pinfunction "BALANCED_PORT_2_6") (pintype "bidirectional"))
    )
    (net (code "34") (name "Net-(FL1-UNBALANCED)") (class "Default")
      (node (ref "AT1") (pin "1") (pinfunction "1_1") (pintype "bidirectional"))
      (node (ref "FL1") (pin "2") (pinfunction "UNBALANCED_2") (pintype "bidirectional"))
    )
    (net (code "35") (name "Net-(IC1-BIAS_FILT)") (class "Default")
      (node (ref "C3") (pin "1") (pinfunction "1_1") (pintype "passive"))
      (node (ref "C4") (pin "1") (pinfunction "1_1") (pintype "passive"))
      (node (ref "IC1") (pin "23") (pinfunction "BIAS_FILT_23") (pintype "bidirectional"))
    )
    (net (code "36") (name "Net-(IC1-CE)") (class "Default")
      (node (ref "IC1") (pin "4") (pinfunction "CE_4") (pintype "bidirectional"))
      (node (ref "R2") (pin "5") (pinfunction "2_5") (pintype "passive"))
    )
    (net (code "37") (name "Net-(IC1-CLK)") (class "Default")
      (node (ref "IC1") (pin "1") (pinfunction "CLK_1") (pintype "bidirectional"))
      (node (ref "R2") (pin "8") (pinfunction "2_8") (pintype "passive"))
    )
    (net (code "38") (name "Net-(IC1-DATA)") (class "Default")
      (node (ref "IC1") (pin "2") (pinfunction "DATA_2") (pintype "bidirectional"))
      (node (ref "R2") (pin "7") (pinfunction "2_7") (pintype "passive"))
    )
    (net (code "39") (name "Net-(IC1-LE)") (class "Default")
      (node (ref "IC1") (pin "3") (pinfunction "LE_3") (pintype "bidirectional"))
      (node (ref "R2") (pin "6") (pinfunction "2_6") (pintype "passive"))
    )
    (net (code "40") (name "Net-(IC1-NOISE_FILT)") (class "Default")
      (node (ref "C1") (pin "1") (pinfunction "1_1") (pintype "passive"))
      (node (ref "C2") (pin "1") (pinfunction "1_1") (pintype "passive"))
      (node (ref "IC1") (pin "19") (pinfunction "NOISE_FILT_19") (pintype "bidirectional"))
    )
    (net (code "41") (name "Net-(IC1-REG)") (class "Default")
      (node (ref "C5") (pin "1") (pinfunction "1_1") (pintype "passive"))
      (node (ref "C6") (pin "1") (pinfunction "1_1") (pintype "passive"))
      (node (ref "IC1") (pin "24") (pinfunction "REG_24") (pintype "bidirectional"))
    )
    (net (code "42") (name "Net-(IC1-RFOUTA_N)") (class "Default")
      (node (ref "C18") (pin "1") (pinfunction "1_1") (pintype "passive"))
      (node (ref "IC1") (pin "13") (pinfunction "RFOUTA_N_13") (pintype "bidirectional"))
      (node (ref "R5") (pin "2") (pinfunction "2_2") (pintype "passive"))
    )
    (net (code "43") (name "Net-(IC1-RFOUTA_P)") (class "Default")
      (node (ref "C17") (pin "1") (pinfunction "1_1") (pintype "passive"))
      (node (ref "IC1") (pin "12") (pinfunction "RFOUTA_P_12") (pintype "bidirectional"))
      (node (ref "R4") (pin "2") (pinfunction "2_2") (pintype "passive"))
    )
    (net (code "44") (name "Net-(IC1-RFOUT_EN)") (class "Default")
      (node (ref "IC1") (pin "26") (pinfunction "RFOUT_EN_26") (pintype "bidirectional"))
      (node (ref "R21") (pin "2") (pinfunction "2_2") (pintype "passive"))
    )
    (net (code "45") (name "Net-(IC1-RSET)") (class "Default")
      (node (ref "IC1") (pin "22") (pinfunction "RSET_22") (pintype "bidirectional"))
      (node (ref "R1") (pin "1") (pinfunction "1_1") (pintype "passive"))
    )
    (net (code "46") (name "Net-(IC1-TUNE)") (class "Default")
      (node (ref "C22") (pin "1") (pinfunction "1_1") (pintype "passive"))
      (node (ref "IC1") (pin "20") (pinfunction "TUNE_20") (pintype "bidirectional"))
      (node (ref "R6") (pin "1") (pinfunction "1_1") (pintype "passive"))
    )
    (net (code "47") (name "Net-(IC2-1G)") (class "Default")
      (node (ref "IC2") (pin "2") (pinfunction "1G_2") (pintype "bidirectional"))
      (node (ref "R16") (pin "1") (pinfunction "1_1") (pintype "passive"))
    )
    (net (code "48") (name "Net-(IC2-VDD)") (class "Default")
      (node (ref "C34") (pin "1") (pinfunction "1_1") (pintype "passive"))
      (node (ref "C35") (pin "1") (pinfunction "1_1") (pintype "passive"))
      (node (ref "IC2") (pin "6") (pinfunction "VDD_6") (pintype "bidirectional"))
      (node (ref "L1") (pin "2") (pinfunction "2_2") (pintype "passive"))
      (node (ref "R16") (pin "2") (pinfunction "2_2") (pintype "passive"))
    )
    (net (code "49") (name "Net-(IC3-1G)") (class "Default")
      (node (ref "IC3") (pin "2") (pinfunction "1G_2") (pintype "bidirectional"))
      (node (ref "R15") (pin "1") (pinfunction "1_1") (pintype "passive"))
    )
    (net (code "50") (name "Net-(IC3-CLKIN)") (class "Default")
      (node (ref "C40") (pin "2") (pinfunction "2_2") (pintype "passive"))
      (node (ref "IC3") (pin "1") (pinfunction "CLKIN_1") (pintype "bidirectional"))
      (node (ref "R23") (pin "2") (pinfunction "2_2") (pintype "passive"))
      (node (ref "R24") (pin "1") (pinfunction "1_1") (pintype "passive"))
    )
    (net (code "51") (name "Net-(IC3-VDD)") (class "Default")
      (node (ref "C31") (pin "1") (pinfunction "1_1") (pintype "passive"))
      (node (ref "C32") (pin "1") (pinfunction "1_1") (pintype "passive"))
      (node (ref "IC3") (pin "6") (pinfunction "VDD_6") (pintype "bidirectional"))
      (node (ref "L2") (pin "2") (pinfunction "2_2") (pintype "passive"))
      (node (ref "R15") (pin "2") (pinfunction "2_2") (pintype "passive"))
    )
    (net (code "52") (name "Net-(IC4-EN)") (class "Default")
      (node (ref "C36") (pin "1") (pinfunction "1_1") (pintype "passive"))
      (node (ref "C38") (pin "1") (pinfunction "1_1") (pintype "passive"))
      (node (ref "IC4") (pin "4") (pinfunction "EN_4") (pintype "bidirectional"))
      (node (ref "IC4") (pin "6") (pinfunction "IN_6") (pintype "bidirectional"))
      (node (ref "L3") (pin "2") (pinfunction "2_2") (pintype "passive"))
    )
    (net (code "53") (name "Net-(IC4-PG)") (class "Default")
      (node (ref "IC4") (pin "3") (pinfunction "PG_3") (pintype "bidirectional"))
      (node (ref "R19") (pin "1") (pinfunction "1_1") (pintype "passive"))
    )
    (net (code "54") (name "Net-(IC6-VREF)") (class "Default")
      (node (ref "C43") (pin "1") (pinfunction "1_1") (pintype "passive"))
      (node (ref "IC6") (pin "6") (pinfunction "VREF_6") (pintype "bidirectional"))
      (node (ref "R24") (pin "2") (pinfunction "2_2") (pintype "passive"))
    )
    (net (code "55") (name "Net-(LED1-PadA)") (class "Default")
      (node (ref "LED1") (pin "A") (pinfunction "A_A") (pintype "passive"))
      (node (ref "R20") (pin "1") (pinfunction "1_1") (pintype "passive"))
    )
    (net (code "56") (name "Net-(U1-PB6(XTAL1{slash}TOSC1))") (class "Default")
      (node (ref "C26") (pin "2") (pinfunction "2_2") (pintype "passive"))
      (node (ref "U1") (pin "7") (pinfunction "PB6(XTAL1/TOSC1)_7") (pintype "bidirectional"))
      (node (ref "Y1") (pin "3") (pinfunction "X2_3") (pintype "bidirectional"))
    )
    (net (code "57") (name "Net-(U1-PB7(XTAL2{slash}TOSC2))") (class "Default")
      (node (ref "C27") (pin "2") (pinfunction "2_2") (pintype "passive"))
      (node (ref "U1") (pin "8") (pinfunction "PB7(XTAL2/TOSC2)_8") (pintype "bidirectional"))
      (node (ref "Y1") (pin "1") (pinfunction "X1_1") (pintype "bidirectional"))
    )
    (net (code "58") (name "PPS_IN") (class "Default")
      (node (ref "IC2") (pin "1") (pinfunction "CLKIN_1") (pintype "bidirectional"))
      (node (ref "J6") (pin "1") (pinfunction "1_1") (pintype "passive"))
      (node (ref "J6") (pin "6") (pinfunction "1_6") (pintype "passive"))
    )
    (net (code "59") (name "PPS_PLL") (class "Default")
      (node (ref "IC2") (pin "3") (pinfunction "Y0_3") (pintype "bidirectional"))
      (node (ref "JP1") (pin "3") (pinfunction "3_3") (pintype "passive"))
    )
    (net (code "60") (name "PPS_RPI") (class "Default")
      (node (ref "IC2") (pin "5") (pinfunction "Y2_5") (pintype "bidirectional"))
      (node (ref "IC7") (pin "3") (pinfunction "A_3") (pintype "bidirectional"))
      (node (ref "J8") (pin "7") (pinfunction "7_7") (pintype "passive"))
    )
    (net (code "61") (name "PPS_USRP") (class "Default")
      (node (ref "IC2") (pin "8") (pinfunction "Y1_8") (pintype "bidirectional"))
      (node (ref "J1") (pin "1") (pinfunction "1_1") (pintype "passive"))
      (node (ref "J1") (pin "6") (pinfunction "1_6") (pintype "passive"))
    )
    (net (code "62") (name "RESET") (class "Default")
      (node (ref "R12") (pin "1") (pinfunction "1_1") (pintype "passive"))
      (node (ref "TP3") (pin "TP") (pinfunction "TP_TP") (pintype "input"))
      (node (ref "U1") (pin "29") (pinfunction "PC6(/RESET)_29") (pintype "bidirectional"))
    )
    (net (code "63") (name "RFOUT_EN") (class "Default")
      (node (ref "R21") (pin "1") (pinfunction "1_1") (pintype "passive"))
      (node (ref "U1") (pin "11") (pinfunction "PD7(AIN1)_11") (pintype "bidirectional"))
    )
    (net (code "64") (name "RF_OUT") (class "Default")
      (node (ref "AT1") (pin "2") (pinfunction "2_2") (pintype "bidirectional"))
      (node (ref "J3") (pin "1") (pinfunction "1_1") (pintype "passive"))
      (node (ref "J3") (pin "6") (pinfunction "1_6") (pintype "passive"))
    )
    (net (code "65") (name "SCL") (class "Default")
      (node (ref "J8") (pin "5") (pinfunction "5_5") (pintype "passive"))
      (node (ref "R18") (pin "1") (pinfunction "1_1") (pintype "passive"))
      (node (ref "U1") (pin "28") (pinfunction "PC5(ADC5/SCL)_28") (pintype "bidirectional"))
    )
    (net (code "66") (name "SDA") (class "Default")
      (node (ref "J8") (pin "4") (pinfunction "4_4") (pintype "passive"))
      (node (ref "R17") (pin "1") (pinfunction "1_1") (pintype "passive"))
      (node (ref "U1") (pin "27") (pinfunction "PC4(ADC4/SDA)_27") (pintype "bidirectional"))
    )
    (net (code "67") (name "SW") (class "Default")
      (node (ref "IC1") (pin "5") (pinfunction "SW_5") (pintype "bidirectional"))
      (node (ref "R7") (pin "1") (pinfunction "1_1") (pintype "passive"))
      (node (ref "R8") (pin "2") (pinfunction "2_2") (pintype "passive"))
    )
    (net (code "68") (name "unconnected-(IC1-RFOUTB_N-Pad15)") (class "Default")
      (node (ref "IC1") (pin "15") (pinfunction "RFOUTB_N_15") (pintype "bidirectional"))
    )
    (net (code "69") (name "unconnected-(IC1-RFOUTB_P-Pad14)") (class "Default")
      (node (ref "IC1") (pin "14") (pinfunction "RFOUTB_P_14") (pintype "bidirectional"))
    )
    (net (code "70") (name "unconnected-(IC2-NC-Pad7)") (class "Default")
      (node (ref "IC2") (pin "7") (pinfunction "NC_7") (pintype "no_connect"))
    )
    (net (code "71") (name "unconnected-(IC3-NC-Pad7)") (class "Default")
      (node (ref "IC3") (pin "7") (pinfunction "NC_7") (pintype "no_connect"))
    )
    (net (code "72") (name "unconnected-(IC4-EP-Pad7)") (class "Default")
      (node (ref "IC4") (pin "7") (pinfunction "EP_7") (pintype "bidirectional"))
    )
    (net (code "73") (name "unconnected-(IC4-NC-Pad2)") (class "Default")
      (node (ref "IC4") (pin "2") (pinfunction "NC_2") (pintype "no_connect"))
    )
    (net (code "74") (name "unconnected-(IC6-NR-Pad5)") (class "Default")
      (node (ref "IC6") (pin "5") (pinfunction "NR_5") (pintype "bidirectional"))
    )
    (net (code "75") (name "unconnected-(U1-AREF-Pad20)") (class "Default")
      (node (ref "U1") (pin "20") (pinfunction "AREF_20") (pintype "bidirectional"))
    )
  )
)
